# RF-PWR-001.net
KiCad netlist of a schematic drawn in EAGLE
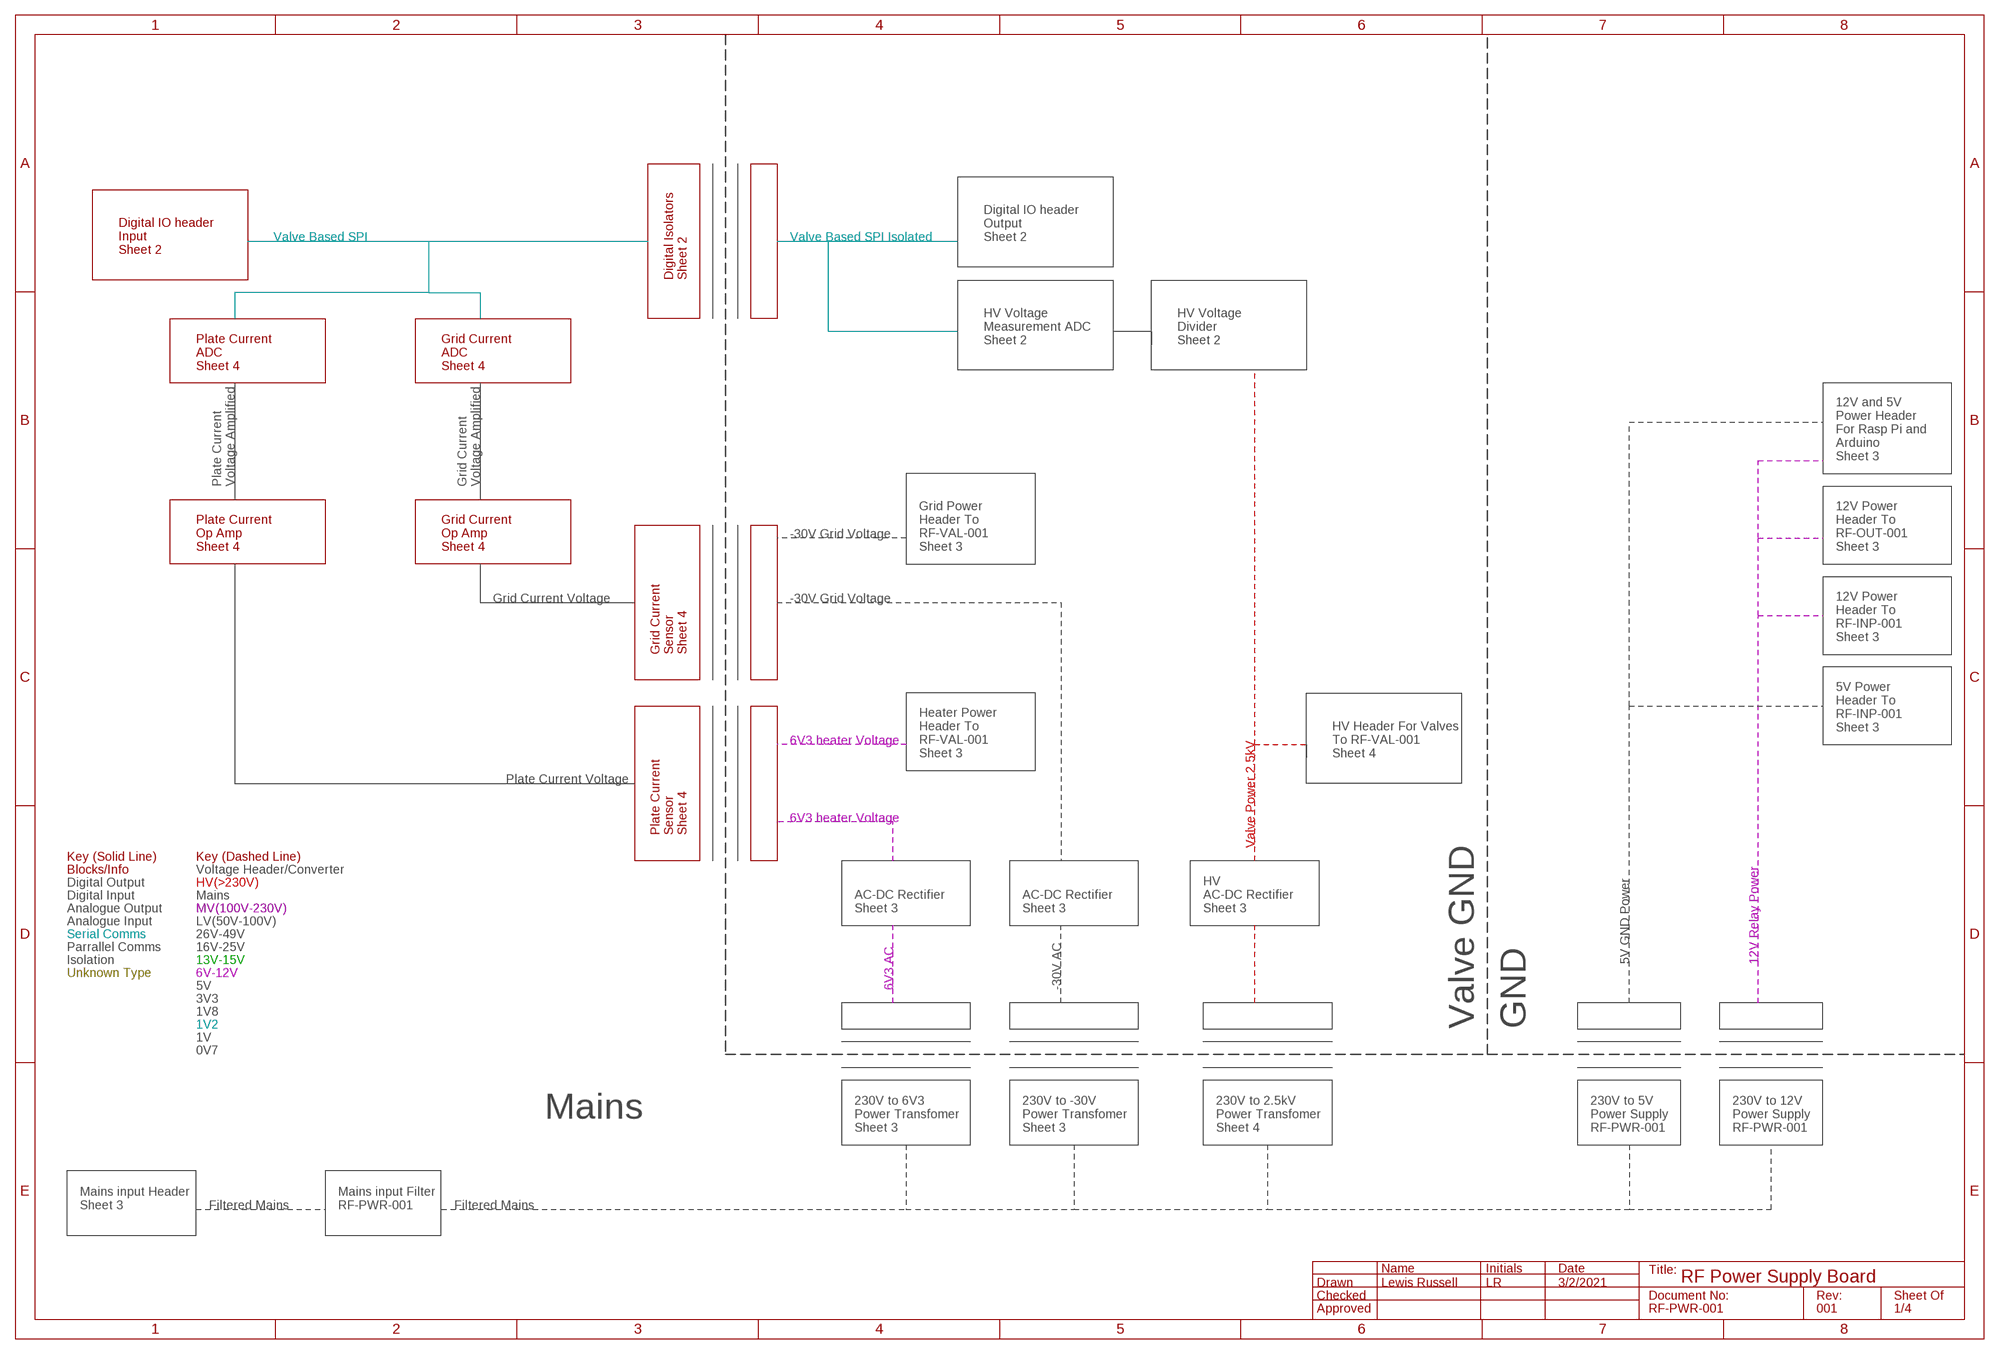
[diagram p0: schematic, sheet 1]
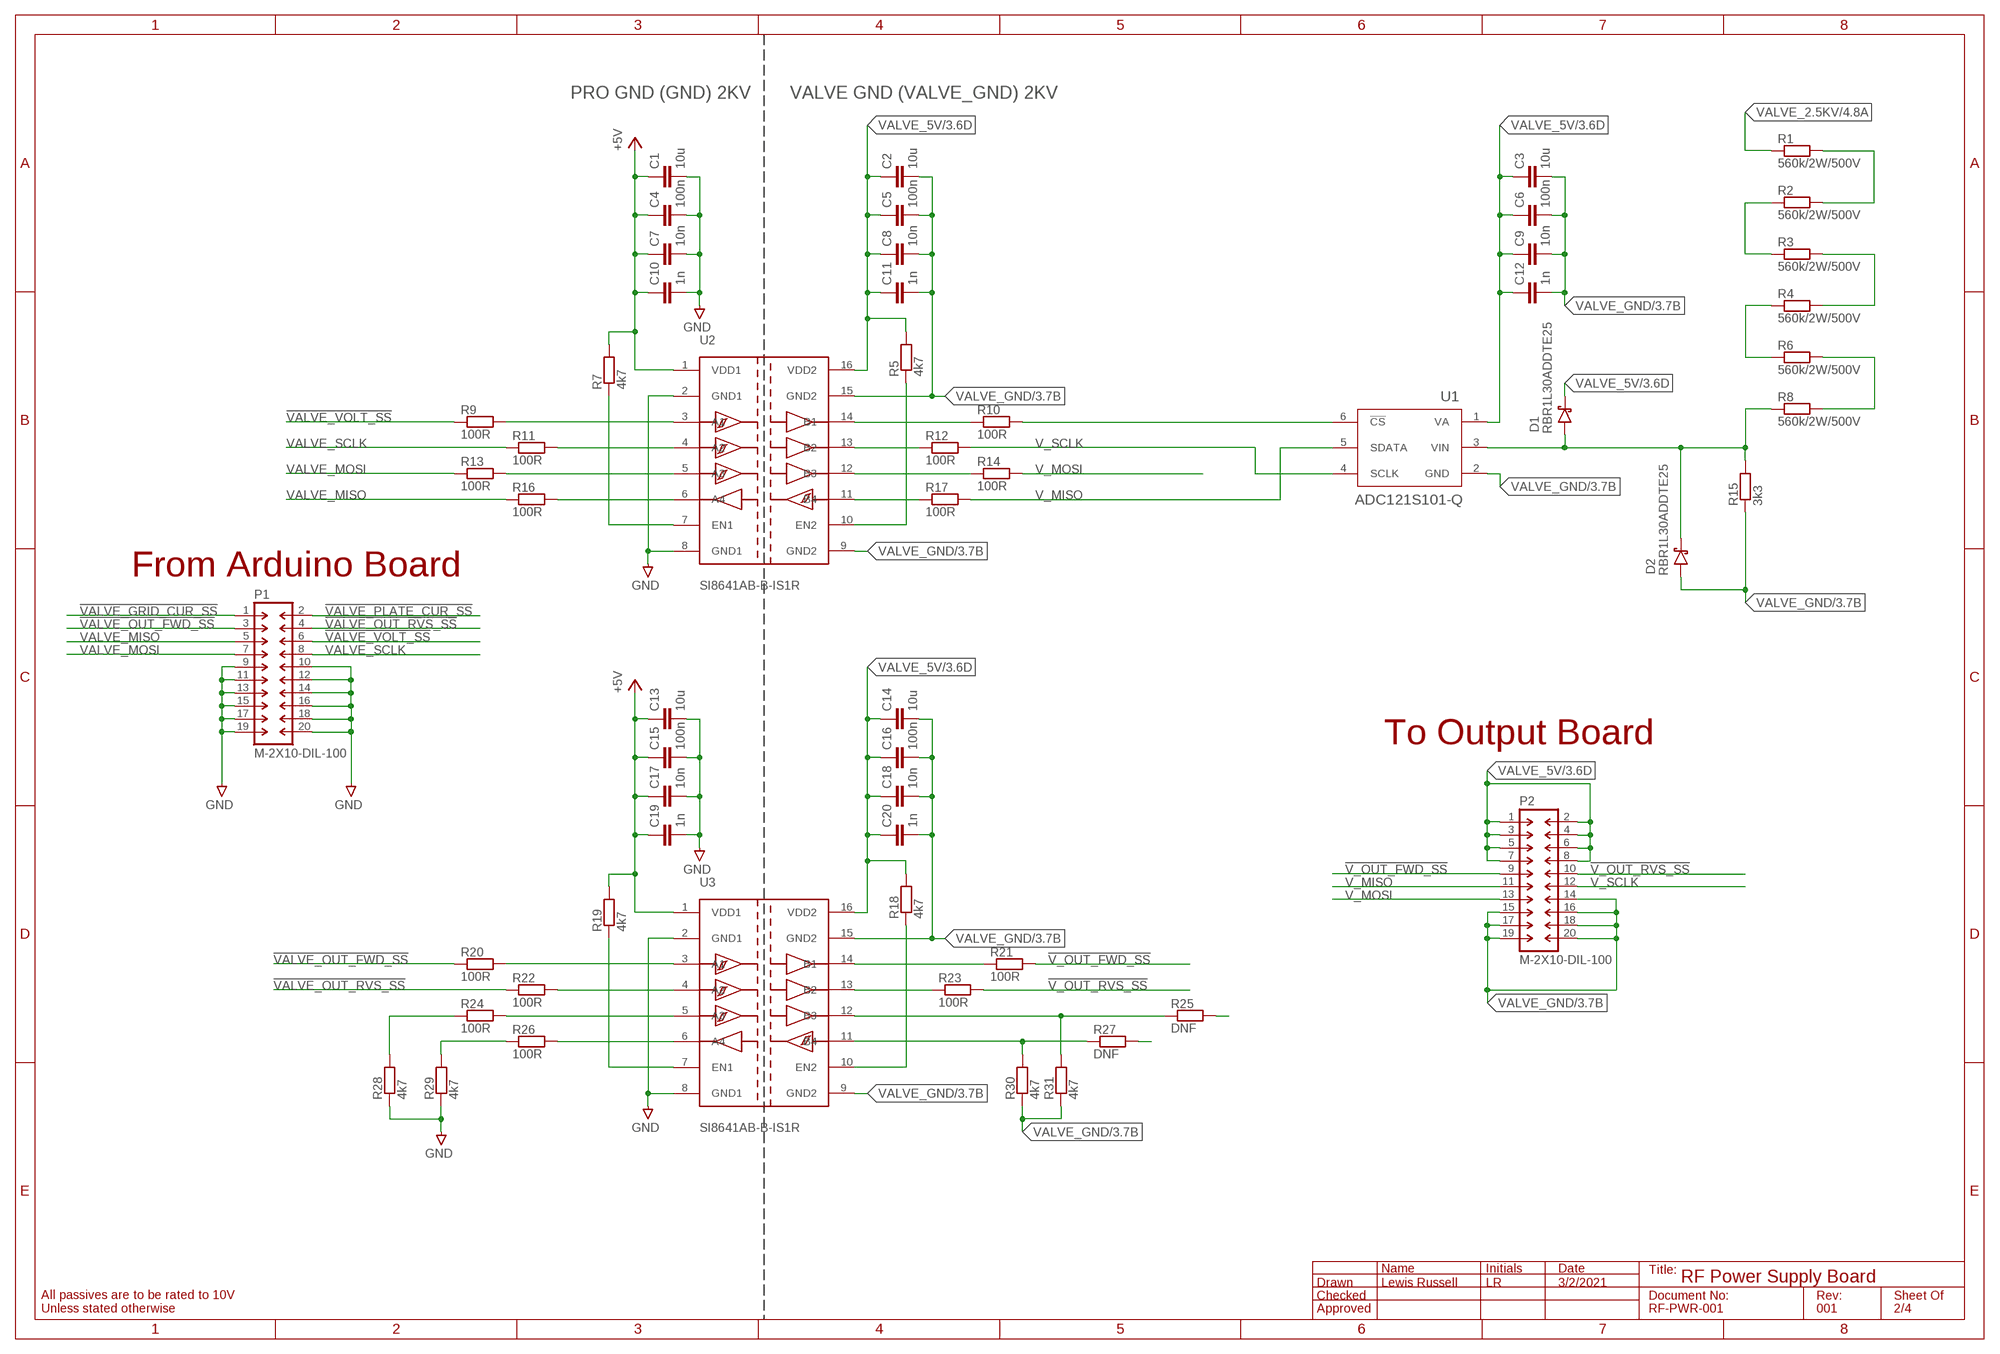
[diagram p1: schematic, sheet 2]
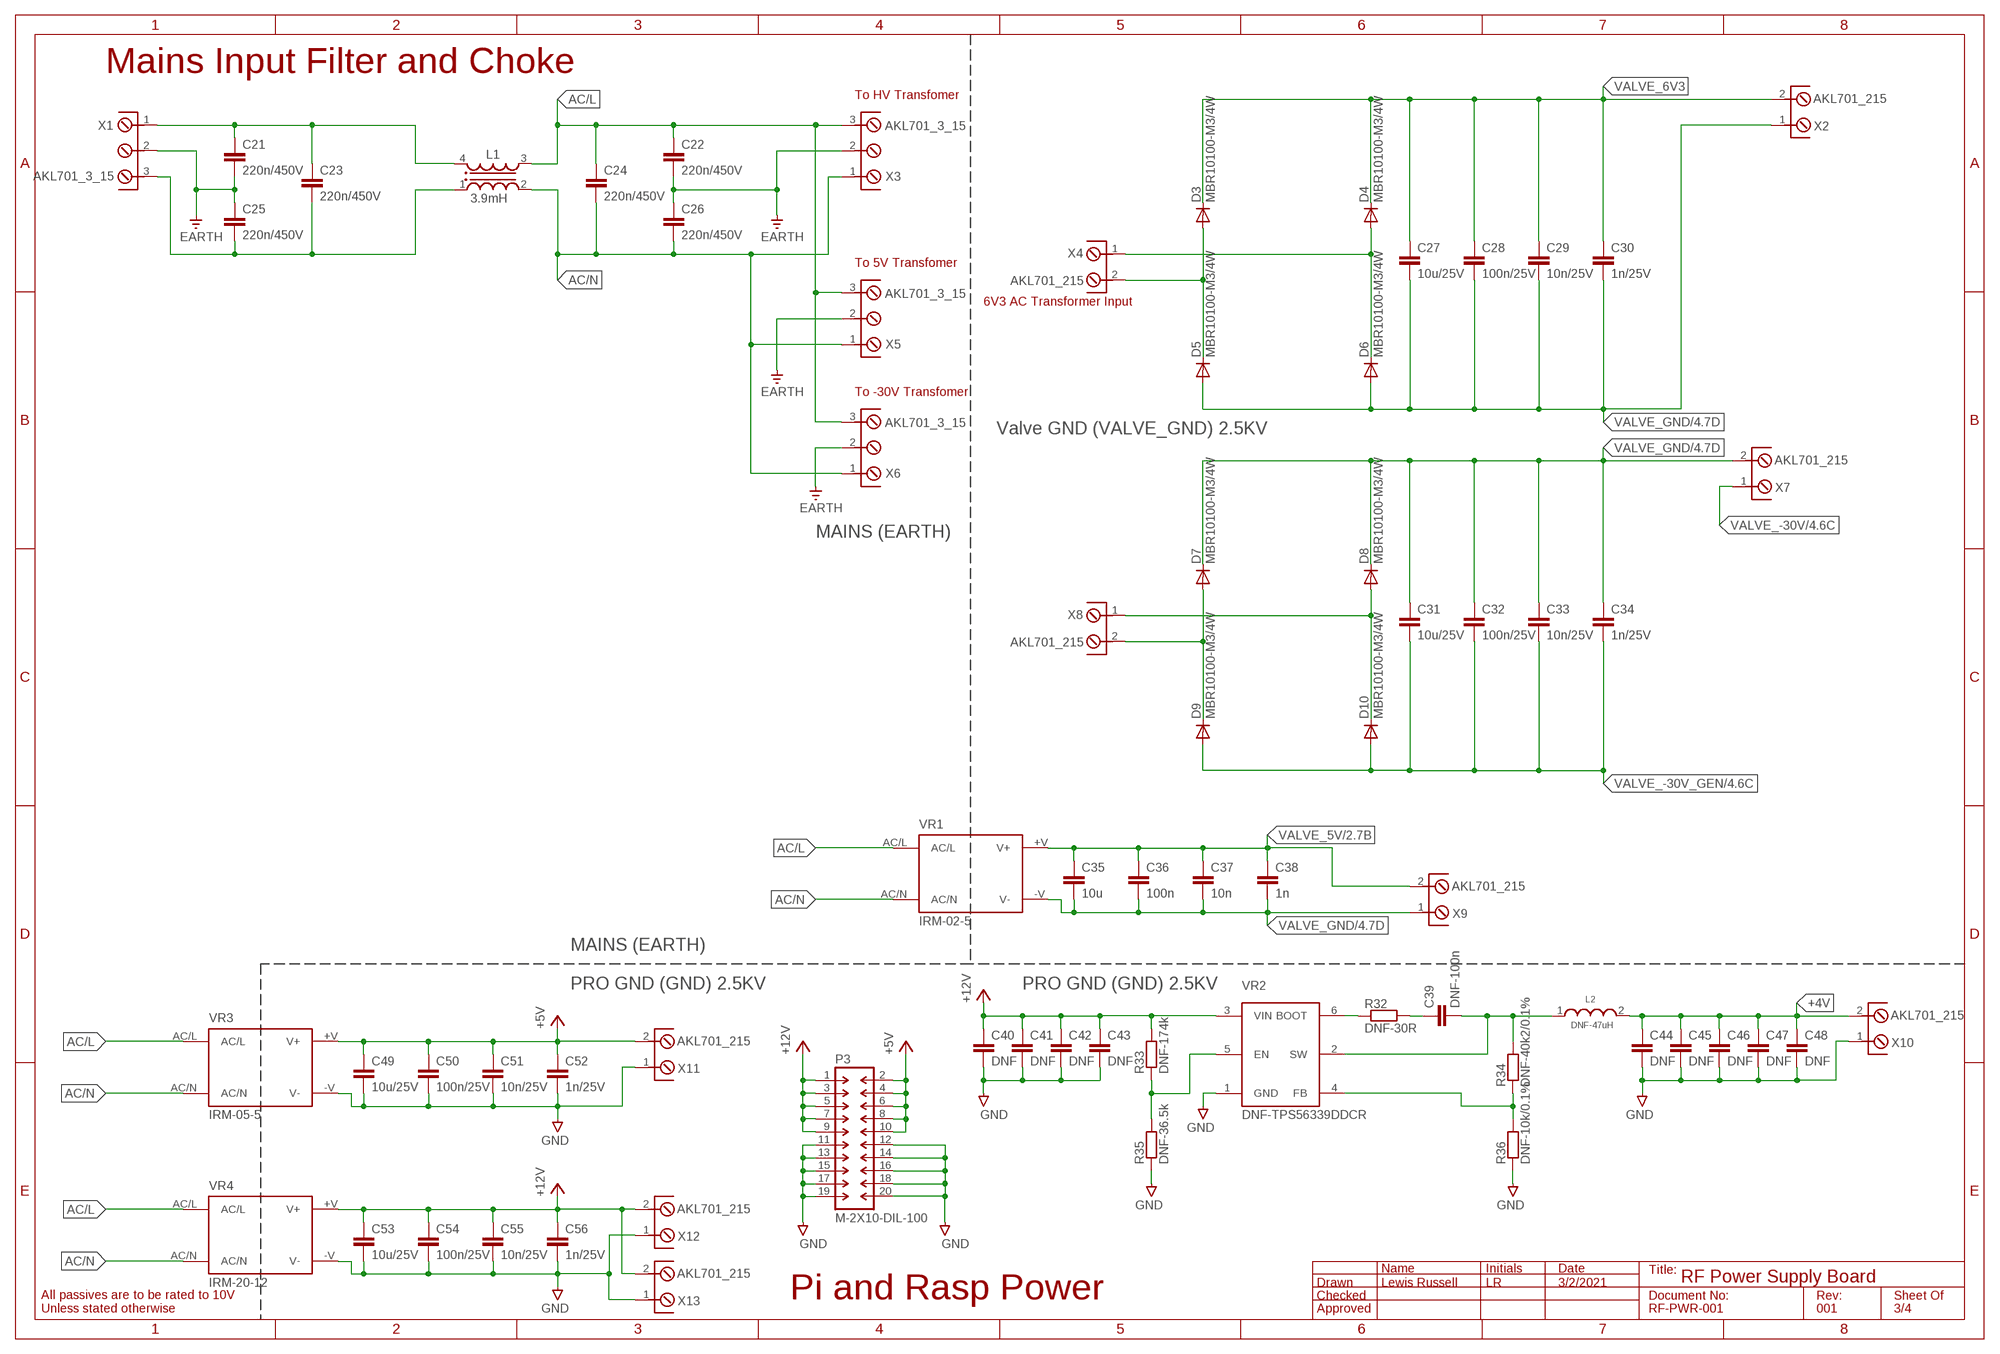
[diagram p2: schematic, sheet 3]
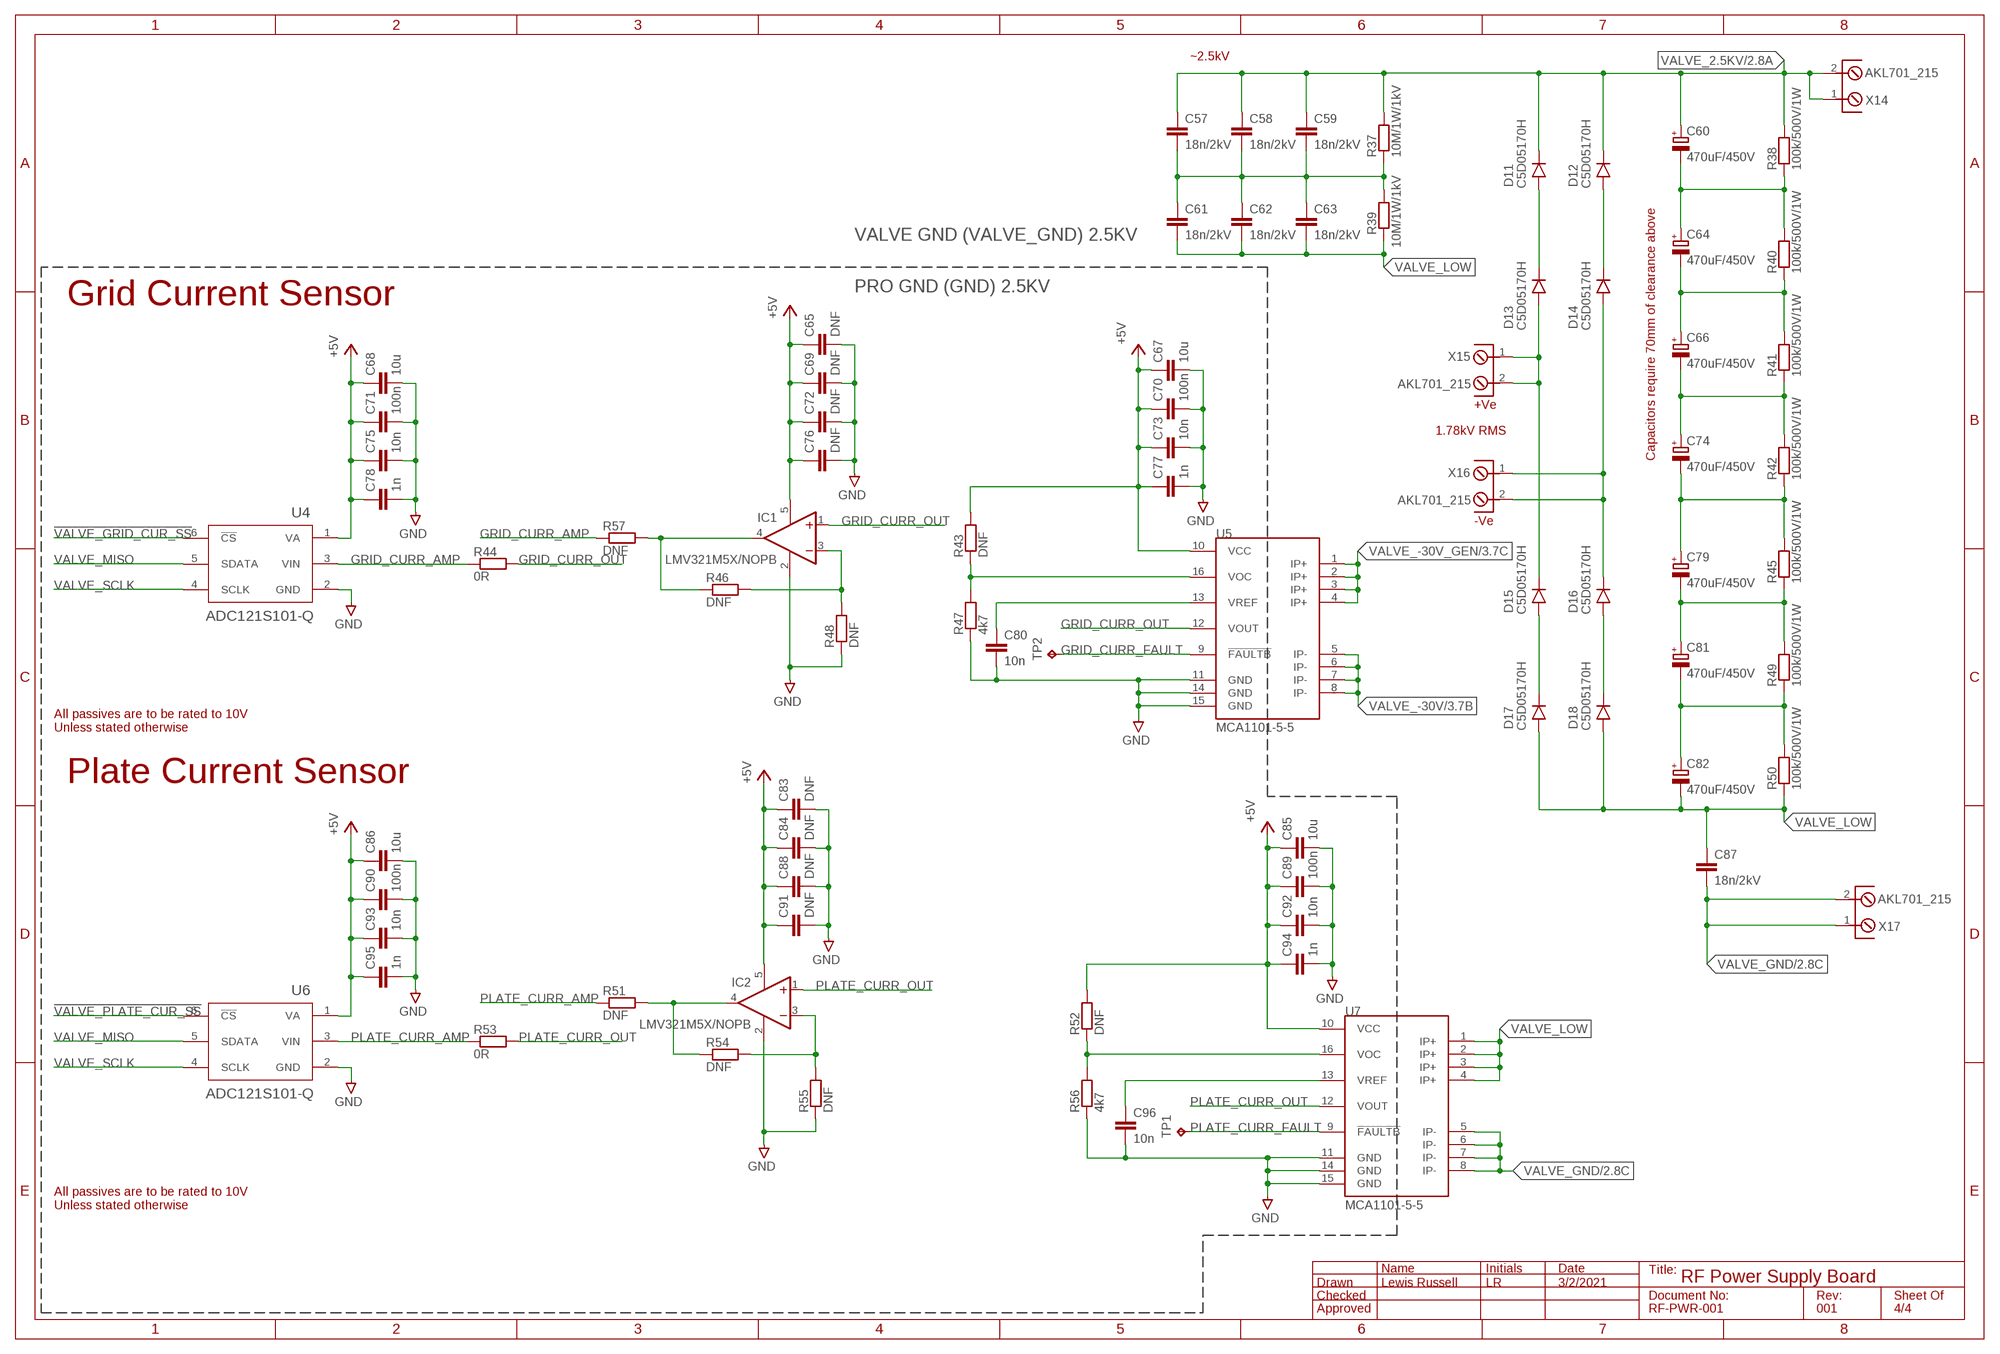
[diagram p3: schematic, sheet 4]

(export (version "E")
  (design (tool "Eeschema 10.0.6"))
  (components
    (comp (ref "C57")
      (value "18n/2kV")
      (footprint "eagle-import:C050-075X075")
      (libsource (lib "eagle-import") (part "C-EU050-075X075"))
    )
    (comp (ref "C58")
      (value "18n/2kV")
      (footprint "eagle-import:C050-075X075")
      (libsource (lib "eagle-import") (part "C-EU050-075X075"))
    )
    (comp (ref "C59")
      (value "18n/2kV")
      (footprint "eagle-import:C050-075X075")
      (libsource (lib "eagle-import") (part "C-EU050-075X075"))
    )
    (comp (ref "C60")
      (value "470uF/450V")
      (footprint "eagle-import:STYLE_D(35MM)")
      (libsource (lib "eagle-import") (part "ALC10D-35MM"))
    )
    (comp (ref "C61")
      (value "18n/2kV")
      (footprint "eagle-import:C050-075X075")
      (libsource (lib "eagle-import") (part "C-EU050-075X075"))
    )
    (comp (ref "C62")
      (value "18n/2kV")
      (footprint "eagle-import:C050-075X075")
      (libsource (lib "eagle-import") (part "C-EU050-075X075"))
    )
    (comp (ref "C63")
      (value "18n/2kV")
      (footprint "eagle-import:C050-075X075")
      (libsource (lib "eagle-import") (part "C-EU050-075X075"))
    )
    (comp (ref "C64")
      (value "470uF/450V")
      (footprint "eagle-import:STYLE_D(35MM)")
      (libsource (lib "eagle-import") (part "ALC10D-35MM"))
    )
    (comp (ref "C65")
      (value "DNF")
      (footprint "eagle-import:C0805")
      (libsource (lib "eagle-import") (part "C-EUC0805"))
    )
    (comp (ref "C66")
      (value "470uF/450V")
      (footprint "eagle-import:STYLE_D(35MM)")
      (libsource (lib "eagle-import") (part "ALC10D-35MM"))
    )
    (comp (ref "C67")
      (value "10u")
      (footprint "eagle-import:C0805")
      (libsource (lib "eagle-import") (part "C-EUC0805"))
    )
    (comp (ref "C68")
      (value "10u")
      (footprint "eagle-import:C0805")
      (libsource (lib "eagle-import") (part "C-EUC0805"))
    )
    (comp (ref "C69")
      (value "DNF")
      (footprint "eagle-import:C0603")
      (libsource (lib "eagle-import") (part "C-EUC0603"))
    )
    (comp (ref "C70")
      (value "100n")
      (footprint "eagle-import:C0603")
      (libsource (lib "eagle-import") (part "C-EUC0603"))
    )
    (comp (ref "C71")
      (value "100n")
      (footprint "eagle-import:C0603")
      (libsource (lib "eagle-import") (part "C-EUC0603"))
    )
    (comp (ref "C72")
      (value "DNF")
      (footprint "eagle-import:C0603")
      (libsource (lib "eagle-import") (part "C-EUC0603"))
    )
    (comp (ref "C73")
      (value "10n")
      (footprint "eagle-import:C0603")
      (libsource (lib "eagle-import") (part "C-EUC0603"))
    )
    (comp (ref "C74")
      (value "470uF/450V")
      (footprint "eagle-import:STYLE_D(35MM)")
      (libsource (lib "eagle-import") (part "ALC10D-35MM"))
    )
    (comp (ref "C75")
      (value "10n")
      (footprint "eagle-import:C0603")
      (libsource (lib "eagle-import") (part "C-EUC0603"))
    )
    (comp (ref "C76")
      (value "DNF")
      (footprint "eagle-import:C0603")
      (libsource (lib "eagle-import") (part "C-EUC0603"))
    )
    (comp (ref "C77")
      (value "1n")
      (footprint "eagle-import:C0603")
      (libsource (lib "eagle-import") (part "C-EUC0603"))
    )
    (comp (ref "C78")
      (value "1n")
      (footprint "eagle-import:C0603")
      (libsource (lib "eagle-import") (part "C-EUC0603"))
    )
    (comp (ref "C79")
      (value "470uF/450V")
      (footprint "eagle-import:STYLE_D(35MM)")
      (libsource (lib "eagle-import") (part "ALC10D-35MM"))
    )
    (comp (ref "C80")
      (value "10n")
      (footprint "eagle-import:C0603")
      (libsource (lib "eagle-import") (part "C-EUC0603"))
    )
    (comp (ref "C81")
      (value "470uF/450V")
      (footprint "eagle-import:STYLE_D(35MM)")
      (libsource (lib "eagle-import") (part "ALC10D-35MM"))
    )
    (comp (ref "C82")
      (value "470uF/450V")
      (footprint "eagle-import:STYLE_D(35MM)")
      (libsource (lib "eagle-import") (part "ALC10D-35MM"))
    )
    (comp (ref "C83")
      (value "DNF")
      (footprint "eagle-import:C0805")
      (libsource (lib "eagle-import") (part "C-EUC0805"))
    )
    (comp (ref "C84")
      (value "DNF")
      (footprint "eagle-import:C0603")
      (libsource (lib "eagle-import") (part "C-EUC0603"))
    )
    (comp (ref "C85")
      (value "10u")
      (footprint "eagle-import:C0805")
      (libsource (lib "eagle-import") (part "C-EUC0805"))
    )
    (comp (ref "C86")
      (value "10u")
      (footprint "eagle-import:C0805")
      (libsource (lib "eagle-import") (part "C-EUC0805"))
    )
    (comp (ref "C87")
      (value "18n/2kV")
      (footprint "eagle-import:C050-075X075")
      (libsource (lib "eagle-import") (part "C-EU050-075X075"))
    )
    (comp (ref "C88")
      (value "DNF")
      (footprint "eagle-import:C0603")
      (libsource (lib "eagle-import") (part "C-EUC0603"))
    )
    (comp (ref "C89")
      (value "100n")
      (footprint "eagle-import:C0603")
      (libsource (lib "eagle-import") (part "C-EUC0603"))
    )
    (comp (ref "C90")
      (value "100n")
      (footprint "eagle-import:C0603")
      (libsource (lib "eagle-import") (part "C-EUC0603"))
    )
    (comp (ref "C91")
      (value "DNF")
      (footprint "eagle-import:C0603")
      (libsource (lib "eagle-import") (part "C-EUC0603"))
    )
    (comp (ref "C92")
      (value "10n")
      (footprint "eagle-import:C0603")
      (libsource (lib "eagle-import") (part "C-EUC0603"))
    )
    (comp (ref "C93")
      (value "10n")
      (footprint "eagle-import:C0603")
      (libsource (lib "eagle-import") (part "C-EUC0603"))
    )
    (comp (ref "C94")
      (value "1n")
      (footprint "eagle-import:C0603")
      (libsource (lib "eagle-import") (part "C-EUC0603"))
    )
    (comp (ref "C95")
      (value "1n")
      (footprint "eagle-import:C0603")
      (libsource (lib "eagle-import") (part "C-EUC0603"))
    )
    (comp (ref "C96")
      (value "10n")
      (footprint "eagle-import:C0603")
      (libsource (lib "eagle-import") (part "C-EUC0603"))
    )
    (comp (ref "D11")
      (value "C5D05170H")
      (footprint "eagle-import:TO-247-2")
      (libsource (lib "eagle-import") (part "DIODEC1A3-2"))
    )
    (comp (ref "D12")
      (value "C5D05170H")
      (footprint "eagle-import:TO-247-2")
      (libsource (lib "eagle-import") (part "DIODEC1A3-2"))
    )
    (comp (ref "D13")
      (value "C5D05170H")
      (footprint "eagle-import:TO-247-2")
      (libsource (lib "eagle-import") (part "DIODEC1A3-2"))
    )
    (comp (ref "D14")
      (value "C5D05170H")
      (footprint "eagle-import:TO-247-2")
      (libsource (lib "eagle-import") (part "DIODEC1A3-2"))
    )
    (comp (ref "D15")
      (value "C5D05170H")
      (footprint "eagle-import:TO-247-2")
      (libsource (lib "eagle-import") (part "DIODEC1A3-2"))
    )
    (comp (ref "D16")
      (value "C5D05170H")
      (footprint "eagle-import:TO-247-2")
      (libsource (lib "eagle-import") (part "DIODEC1A3-2"))
    )
    (comp (ref "D17")
      (value "C5D05170H")
      (footprint "eagle-import:TO-247-2")
      (libsource (lib "eagle-import") (part "DIODEC1A3-2"))
    )
    (comp (ref "D18")
      (value "C5D05170H")
      (footprint "eagle-import:TO-247-2")
      (libsource (lib "eagle-import") (part "DIODEC1A3-2"))
    )
    (comp (ref "IC1")
      (value "LMV321M5X/NOPB")
      (footprint "eagle-import:SOT23-5")
      (libsource (lib "eagle-import") (part "LMV321?M5"))
    )
    (comp (ref "IC2")
      (value "LMV321M5X/NOPB")
      (footprint "eagle-import:SOT23-5")
      (libsource (lib "eagle-import") (part "LMV321?M5"))
    )
    (comp (ref "R37")
      (value "10M/1W/1kV")
      (footprint "eagle-import:R2512")
      (libsource (lib "eagle-import") (part "R-EUR2512"))
    )
    (comp (ref "R38")
      (value "100k/500V/1W")
      (footprint "eagle-import:R2512")
      (libsource (lib "eagle-import") (part "R-EUR2512"))
    )
    (comp (ref "R39")
      (value "10M/1W/1kV")
      (footprint "eagle-import:R2512")
      (libsource (lib "eagle-import") (part "R-EUR2512"))
    )
    (comp (ref "R40")
      (value "100k/500V/1W")
      (footprint "eagle-import:R2512")
      (libsource (lib "eagle-import") (part "R-EUR2512"))
    )
    (comp (ref "R41")
      (value "100k/500V/1W")
      (footprint "eagle-import:R2512")
      (libsource (lib "eagle-import") (part "R-EUR2512"))
    )
    (comp (ref "R42")
      (value "100k/500V/1W")
      (footprint "eagle-import:R2512")
      (libsource (lib "eagle-import") (part "R-EUR2512"))
    )
    (comp (ref "R43")
      (value "DNF")
      (footprint "eagle-import:R0603")
      (libsource (lib "eagle-import") (part "R-EUR0603"))
    )
    (comp (ref "R44")
      (value "0R")
      (footprint "eagle-import:R0603")
      (libsource (lib "eagle-import") (part "R-EUR0603"))
    )
    (comp (ref "R45")
      (value "100k/500V/1W")
      (footprint "eagle-import:R2512")
      (libsource (lib "eagle-import") (part "R-EUR2512"))
    )
    (comp (ref "R46")
      (value "DNF")
      (footprint "eagle-import:R0603")
      (libsource (lib "eagle-import") (part "R-EUR0603"))
    )
    (comp (ref "R47")
      (value "4k7")
      (footprint "eagle-import:R0603")
      (libsource (lib "eagle-import") (part "R-EUR0603"))
    )
    (comp (ref "R48")
      (value "DNF")
      (footprint "eagle-import:R0603")
      (libsource (lib "eagle-import") (part "R-EUR0603"))
    )
    (comp (ref "R49")
      (value "100k/500V/1W")
      (footprint "eagle-import:R2512")
      (libsource (lib "eagle-import") (part "R-EUR2512"))
    )
    (comp (ref "R50")
      (value "100k/500V/1W")
      (footprint "eagle-import:R2512")
      (libsource (lib "eagle-import") (part "R-EUR2512"))
    )
    (comp (ref "R51")
      (value "DNF")
      (footprint "eagle-import:R0603")
      (libsource (lib "eagle-import") (part "R-EUR0603"))
    )
    (comp (ref "R52")
      (value "DNF")
      (footprint "eagle-import:R0603")
      (libsource (lib "eagle-import") (part "R-EUR0603"))
    )
    (comp (ref "R53")
      (value "0R")
      (footprint "eagle-import:R0603")
      (libsource (lib "eagle-import") (part "R-EUR0603"))
    )
    (comp (ref "R54")
      (value "DNF")
      (footprint "eagle-import:R0603")
      (libsource (lib "eagle-import") (part "R-EUR0603"))
    )
    (comp (ref "R55")
      (value "DNF")
      (footprint "eagle-import:R0603")
      (libsource (lib "eagle-import") (part "R-EUR0603"))
    )
    (comp (ref "R56")
      (value "4k7")
      (footprint "eagle-import:R0603")
      (libsource (lib "eagle-import") (part "R-EUR0603"))
    )
    (comp (ref "R57")
      (value "DNF")
      (footprint "eagle-import:R0603")
      (libsource (lib "eagle-import") (part "R-EUR0603"))
    )
    (comp (ref "TP1")
      (value "TPTP16R")
      (footprint "eagle-import:TP16R")
      (libsource (lib "eagle-import") (part "TPTP16R"))
    )
    (comp (ref "TP2")
      (value "TPTP16R")
      (footprint "eagle-import:TP16R")
      (libsource (lib "eagle-import") (part "TPTP16R"))
    )
    (comp (ref "U4")
      (value "ADC121S101-Q")
      (footprint "eagle-import:SOT23-6")
      (libsource (lib "eagle-import") (part "ADC121S101-Q"))
    )
    (comp (ref "U5")
      (value "MCA1101-5-5")
      (footprint "eagle-import:SOIC_16")
      (libsource (lib "eagle-import") (part "MCA1101-5-5"))
    )
    (comp (ref "U6")
      (value "ADC121S101-Q")
      (footprint "eagle-import:SOT23-6")
      (libsource (lib "eagle-import") (part "ADC121S101-Q"))
    )
    (comp (ref "U7")
      (value "MCA1101-5-5")
      (footprint "eagle-import:SOIC_16")
      (libsource (lib "eagle-import") (part "MCA1101-5-5"))
    )
    (comp (ref "X14")
      (value "AKL701_215")
      (footprint "eagle-import:AKL701_2_15")
      (libsource (lib "eagle-import") (part "AKL701_215"))
    )
    (comp (ref "X15")
      (value "AKL701_215")
      (footprint "eagle-import:AKL701_2_15")
      (libsource (lib "eagle-import") (part "AKL701_215"))
    )
    (comp (ref "X16")
      (value "AKL701_215")
      (footprint "eagle-import:AKL701_2_15")
      (libsource (lib "eagle-import") (part "AKL701_215"))
    )
    (comp (ref "X17")
      (value "AKL701_215")
      (footprint "eagle-import:AKL701_2_15")
      (libsource (lib "eagle-import") (part "AKL701_215"))
    )
    (comp (ref "C21")
      (value "220n/450V")
      (footprint "eagle-import:C1210")
      (libsource (lib "eagle-import") (part "C-EUC1210"))
    )
    (comp (ref "C22")
      (value "220n/450V")
      (footprint "eagle-import:C1210")
      (libsource (lib "eagle-import") (part "C-EUC1210"))
    )
    (comp (ref "C23")
      (value "220n/450V")
      (footprint "eagle-import:C1210")
      (libsource (lib "eagle-import") (part "C-EUC1210"))
    )
    (comp (ref "C24")
      (value "220n/450V")
      (footprint "eagle-import:C1210")
      (libsource (lib "eagle-import") (part "C-EUC1210"))
    )
    (comp (ref "C25")
      (value "220n/450V")
      (footprint "eagle-import:C1210")
      (libsource (lib "eagle-import") (part "C-EUC1210"))
    )
    (comp (ref "C26")
      (value "220n/450V")
      (footprint "eagle-import:C1210")
      (libsource (lib "eagle-import") (part "C-EUC1210"))
    )
    (comp (ref "C27")
      (value "10u/25V")
      (footprint "eagle-import:C0805")
      (libsource (lib "eagle-import") (part "C-EUC0805"))
    )
    (comp (ref "C28")
      (value "100n/25V")
      (footprint "eagle-import:C0603")
      (libsource (lib "eagle-import") (part "C-EUC0603"))
    )
    (comp (ref "C29")
      (value "10n/25V")
      (footprint "eagle-import:C0603")
      (libsource (lib "eagle-import") (part "C-EUC0603"))
    )
    (comp (ref "C30")
      (value "1n/25V")
      (footprint "eagle-import:C0603")
      (libsource (lib "eagle-import") (part "C-EUC0603"))
    )
    (comp (ref "C31")
      (value "10u/25V")
      (footprint "eagle-import:C0805")
      (libsource (lib "eagle-import") (part "C-EUC0805"))
    )
    (comp (ref "C32")
      (value "100n/25V")
      (footprint "eagle-import:C0603")
      (libsource (lib "eagle-import") (part "C-EUC0603"))
    )
    (comp (ref "C33")
      (value "10n/25V")
      (footprint "eagle-import:C0603")
      (libsource (lib "eagle-import") (part "C-EUC0603"))
    )
    (comp (ref "C34")
      (value "1n/25V")
      (footprint "eagle-import:C0603")
      (libsource (lib "eagle-import") (part "C-EUC0603"))
    )
    (comp (ref "C35")
      (value "10u")
      (footprint "eagle-import:C0805")
      (libsource (lib "eagle-import") (part "C-EUC0805"))
    )
    (comp (ref "C36")
      (value "100n")
      (footprint "eagle-import:C0603")
      (libsource (lib "eagle-import") (part "C-EUC0603"))
    )
    (comp (ref "C37")
      (value "10n")
      (footprint "eagle-import:C0603")
      (libsource (lib "eagle-import") (part "C-EUC0603"))
    )
    (comp (ref "C38")
      (value "1n")
      (footprint "eagle-import:C0603")
      (libsource (lib "eagle-import") (part "C-EUC0603"))
    )
    (comp (ref "C39")
      (value "DNF-100n")
      (footprint "eagle-import:C0603")
      (libsource (lib "eagle-import") (part "C-EUC0603"))
    )
    (comp (ref "C40")
      (value "DNF")
      (footprint "eagle-import:C0805")
      (libsource (lib "eagle-import") (part "C-EUC0805"))
    )
    (comp (ref "C41")
      (value "DNF")
      (footprint "eagle-import:C0603")
      (libsource (lib "eagle-import") (part "C-EUC0603"))
    )
    (comp (ref "C42")
      (value "DNF")
      (footprint "eagle-import:C0603")
      (libsource (lib "eagle-import") (part "C-EUC0603"))
    )
    (comp (ref "C43")
      (value "DNF")
      (footprint "eagle-import:C0603")
      (libsource (lib "eagle-import") (part "C-EUC0603"))
    )
    (comp (ref "C44")
      (value "DNF")
      (footprint "eagle-import:C1206")
      (libsource (lib "eagle-import") (part "C-EUC1206"))
    )
    (comp (ref "C45")
      (value "DNF")
      (footprint "eagle-import:C0805")
      (libsource (lib "eagle-import") (part "C-EUC0805"))
    )
    (comp (ref "C46")
      (value "DNF")
      (footprint "eagle-import:C0603")
      (libsource (lib "eagle-import") (part "C-EUC0603"))
    )
    (comp (ref "C47")
      (value "DNF")
      (footprint "eagle-import:C0603")
      (libsource (lib "eagle-import") (part "C-EUC0603"))
    )
    (comp (ref "C48")
      (value "DNF")
      (footprint "eagle-import:C0603")
      (libsource (lib "eagle-import") (part "C-EUC0603"))
    )
    (comp (ref "C49")
      (value "10u/25V")
      (footprint "eagle-import:C0805")
      (libsource (lib "eagle-import") (part "C-EUC0805"))
    )
    (comp (ref "C50")
      (value "100n/25V")
      (footprint "eagle-import:C0603")
      (libsource (lib "eagle-import") (part "C-EUC0603"))
    )
    (comp (ref "C51")
      (value "10n/25V")
      (footprint "eagle-import:C0603")
      (libsource (lib "eagle-import") (part "C-EUC0603"))
    )
    (comp (ref "C52")
      (value "1n/25V")
      (footprint "eagle-import:C0603")
      (libsource (lib "eagle-import") (part "C-EUC0603"))
    )
    (comp (ref "C53")
      (value "10u/25V")
      (footprint "eagle-import:C0805")
      (libsource (lib "eagle-import") (part "C-EUC0805"))
    )
    (comp (ref "C54")
      (value "100n/25V")
      (footprint "eagle-import:C0603")
      (libsource (lib "eagle-import") (part "C-EUC0603"))
    )
    (comp (ref "C55")
      (value "10n/25V")
      (footprint "eagle-import:C0603")
      (libsource (lib "eagle-import") (part "C-EUC0603"))
    )
    (comp (ref "C56")
      (value "1n/25V")
      (footprint "eagle-import:C0603")
      (libsource (lib "eagle-import") (part "C-EUC0603"))
    )
    (comp (ref "D3")
      (value "MBR10100-M3/4W")
      (footprint "eagle-import:TO220ACS")
      (libsource (lib "eagle-import") (part "DIODE-TO220V"))
    )
    (comp (ref "D4")
      (value "MBR10100-M3/4W")
      (footprint "eagle-import:TO220ACS")
      (libsource (lib "eagle-import") (part "DIODE-TO220V"))
    )
    (comp (ref "D5")
      (value "MBR10100-M3/4W")
      (footprint "eagle-import:TO220ACS")
      (libsource (lib "eagle-import") (part "DIODE-TO220V"))
    )
    (comp (ref "D6")
      (value "MBR10100-M3/4W")
      (footprint "eagle-import:TO220ACS")
      (libsource (lib "eagle-import") (part "DIODE-TO220V"))
    )
    (comp (ref "D7")
      (value "MBR10100-M3/4W")
      (footprint "eagle-import:TO220ACS")
      (libsource (lib "eagle-import") (part "DIODE-TO220V"))
    )
    (comp (ref "D8")
      (value "MBR10100-M3/4W")
      (footprint "eagle-import:TO220ACS")
      (libsource (lib "eagle-import") (part "DIODE-TO220V"))
    )
    (comp (ref "D9")
      (value "MBR10100-M3/4W")
      (footprint "eagle-import:TO220ACS")
      (libsource (lib "eagle-import") (part "DIODE-TO220V"))
    )
    (comp (ref "D10")
      (value "MBR10100-M3/4W")
      (footprint "eagle-import:TO220ACS")
      (libsource (lib "eagle-import") (part "DIODE-TO220V"))
    )
    (comp (ref "L1")
      (value "3.9mH")
      (footprint "eagle-import:WE-FCL_ET35")
      (libsource (lib "eagle-import") (part "WE-FCL_ET35_744866392"))
    )
    (comp (ref "L2")
      (value "DNF-47uH")
      (footprint "eagle-import:WE-HCF_2920_ROUND")
      (libsource (lib "eagle-import") (part "WE-HCF_2920_ROUND_74437529203470"))
    )
    (comp (ref "P3")
      (value "M-2X10-DIL-100")
      (footprint "eagle-import:DIL-100-2X10")
      (libsource (lib "eagle-import") (part "M-2X10-DIL-100"))
    )
    (comp (ref "R32")
      (value "DNF-30R")
      (footprint "eagle-import:R0603")
      (libsource (lib "eagle-import") (part "R-EUR0603"))
    )
    (comp (ref "R33")
      (value "DNF-174k")
      (footprint "eagle-import:R0603")
      (libsource (lib "eagle-import") (part "R-EUR0603"))
    )
    (comp (ref "R34")
      (value "DNF-40k2/0.1%")
      (footprint "eagle-import:R0603")
      (libsource (lib "eagle-import") (part "R-EUR0603"))
    )
    (comp (ref "R35")
      (value "DNF-36.5k")
      (footprint "eagle-import:R0603")
      (libsource (lib "eagle-import") (part "R-EUR0603"))
    )
    (comp (ref "R36")
      (value "DNF-10k/0.1%")
      (footprint "eagle-import:R0603")
      (libsource (lib "eagle-import") (part "R-EUR0603"))
    )
    (comp (ref "VR1")
      (value "IRM-02-5")
      (footprint "eagle-import:IRM_1-2_TH")
      (libsource (lib "eagle-import") (part "IRM-02-5"))
    )
    (comp (ref "VR2")
      (value "DNF-TPS56339DDCR")
      (footprint "eagle-import:SOT23-6")
      (libsource (lib "eagle-import") (part "TPS56339DDCR"))
    )
    (comp (ref "VR3")
      (value "IRM-05-5")
      (footprint "eagle-import:IRM_5-10_TH")
      (libsource (lib "eagle-import") (part "IRM-05-5"))
    )
    (comp (ref "VR4")
      (value "IRM-20-12")
      (footprint "eagle-import:IRM_15-20_TH")
      (libsource (lib "eagle-import") (part "IRM-20-12"))
    )
    (comp (ref "X1")
      (value "AKL701_3_15")
      (footprint "eagle-import:AKL701_3_15")
      (libsource (lib "eagle-import") (part "AKL701_3_15"))
    )
    (comp (ref "X2")
      (value "AKL701_215")
      (footprint "eagle-import:AKL701_2_15")
      (libsource (lib "eagle-import") (part "AKL701_215"))
    )
    (comp (ref "X3")
      (value "AKL701_3_15")
      (footprint "eagle-import:AKL701_3_15")
      (libsource (lib "eagle-import") (part "AKL701_3_15"))
    )
    (comp (ref "X4")
      (value "AKL701_215")
      (footprint "eagle-import:AKL701_2_15")
      (libsource (lib "eagle-import") (part "AKL701_215"))
    )
    (comp (ref "X5")
      (value "AKL701_3_15")
      (footprint "eagle-import:AKL701_3_15")
      (libsource (lib "eagle-import") (part "AKL701_3_15"))
    )
    (comp (ref "X6")
      (value "AKL701_3_15")
      (footprint "eagle-import:AKL701_3_15")
      (libsource (lib "eagle-import") (part "AKL701_3_15"))
    )
    (comp (ref "X7")
      (value "AKL701_215")
      (footprint "eagle-import:AKL701_2_15")
      (libsource (lib "eagle-import") (part "AKL701_215"))
    )
    (comp (ref "X8")
      (value "AKL701_215")
      (footprint "eagle-import:AKL701_2_15")
      (libsource (lib "eagle-import") (part "AKL701_215"))
    )
    (comp (ref "X9")
      (value "AKL701_215")
      (footprint "eagle-import:AKL701_2_15")
      (libsource (lib "eagle-import") (part "AKL701_215"))
    )
    (comp (ref "X10")
      (value "AKL701_215")
      (footprint "eagle-import:AKL701_2_15")
      (libsource (lib "eagle-import") (part "AKL701_215"))
    )
    (comp (ref "X11")
      (value "AKL701_215")
      (footprint "eagle-import:AKL701_2_15")
      (libsource (lib "eagle-import") (part "AKL701_215"))
    )
    (comp (ref "X12")
      (value "AKL701_215")
      (footprint "eagle-import:AKL701_2_15")
      (libsource (lib "eagle-import") (part "AKL701_215"))
    )
    (comp (ref "X13")
      (value "AKL701_215")
      (footprint "eagle-import:AKL701_2_15")
      (libsource (lib "eagle-import") (part "AKL701_215"))
    )
    (comp (ref "C1")
      (value "10u")
      (footprint "eagle-import:C0805")
      (libsource (lib "eagle-import") (part "C-EUC0805"))
    )
    (comp (ref "C2")
      (value "10u")
      (footprint "eagle-import:C0805")
      (libsource (lib "eagle-import") (part "C-EUC0805"))
    )
    (comp (ref "C3")
      (value "10u")
      (footprint "eagle-import:C0805")
      (libsource (lib "eagle-import") (part "C-EUC0805"))
    )
    (comp (ref "C4")
      (value "100n")
      (footprint "eagle-import:C0603")
      (libsource (lib "eagle-import") (part "C-EUC0603"))
    )
    (comp (ref "C5")
      (value "100n")
      (footprint "eagle-import:C0603")
      (libsource (lib "eagle-import") (part "C-EUC0603"))
    )
    (comp (ref "C6")
      (value "100n")
      (footprint "eagle-import:C0603")
      (libsource (lib "eagle-import") (part "C-EUC0603"))
    )
    (comp (ref "C7")
      (value "10n")
      (footprint "eagle-import:C0603")
      (libsource (lib "eagle-import") (part "C-EUC0603"))
    )
    (comp (ref "C8")
      (value "10n")
      (footprint "eagle-import:C0603")
      (libsource (lib "eagle-import") (part "C-EUC0603"))
    )
    (comp (ref "C9")
      (value "10n")
      (footprint "eagle-import:C0603")
      (libsource (lib "eagle-import") (part "C-EUC0603"))
    )
    (comp (ref "C10")
      (value "1n")
      (footprint "eagle-import:C0603")
      (libsource (lib "eagle-import") (part "C-EUC0603"))
    )
    (comp (ref "C11")
      (value "1n")
      (footprint "eagle-import:C0603")
      (libsource (lib "eagle-import") (part "C-EUC0603"))
    )
    (comp (ref "C12")
      (value "1n")
      (footprint "eagle-import:C0603")
      (libsource (lib "eagle-import") (part "C-EUC0603"))
    )
    (comp (ref "C13")
      (value "10u")
      (footprint "eagle-import:C0805")
      (libsource (lib "eagle-import") (part "C-EUC0805"))
    )
    (comp (ref "C14")
      (value "10u")
      (footprint "eagle-import:C0805")
      (libsource (lib "eagle-import") (part "C-EUC0805"))
    )
    (comp (ref "C15")
      (value "100n")
      (footprint "eagle-import:C0603")
      (libsource (lib "eagle-import") (part "C-EUC0603"))
    )
    (comp (ref "C16")
      (value "100n")
      (footprint "eagle-import:C0603")
      (libsource (lib "eagle-import") (part "C-EUC0603"))
    )
    (comp (ref "C17")
      (value "10n")
      (footprint "eagle-import:C0603")
      (libsource (lib "eagle-import") (part "C-EUC0603"))
    )
    (comp (ref "C18")
      (value "10n")
      (footprint "eagle-import:C0603")
      (libsource (lib "eagle-import") (part "C-EUC0603"))
    )
    (comp (ref "C19")
      (value "1n")
      (footprint "eagle-import:C0603")
      (libsource (lib "eagle-import") (part "C-EUC0603"))
    )
    (comp (ref "C20")
      (value "1n")
      (footprint "eagle-import:C0603")
      (libsource (lib "eagle-import") (part "C-EUC0603"))
    )
    (comp (ref "D1")
      (value "RBR1L30ADDTE25")
      (footprint "eagle-import:SMA_DO-214AC")
      (libsource (lib "eagle-import") (part "SCHOTTKY_DIODESMA"))
    )
    (comp (ref "D2")
      (value "RBR1L30ADDTE25")
      (footprint "eagle-import:SMA_DO-214AC")
      (libsource (lib "eagle-import") (part "SCHOTTKY_DIODESMA"))
    )
    (comp (ref "P1")
      (value "M-2X10-DIL-100")
      (footprint "eagle-import:DIL-100-2X10")
      (libsource (lib "eagle-import") (part "M-2X10-DIL-100"))
    )
    (comp (ref "P2")
      (value "M-2X10-DIL-100")
      (footprint "eagle-import:DIL-100-2X10")
      (libsource (lib "eagle-import") (part "M-2X10-DIL-100"))
    )
    (comp (ref "R1")
      (value "560k/2W/500V")
      (footprint "eagle-import:SMV1_SMF2")
      (libsource (lib "eagle-import") (part "R-EU_SMF2"))
    )
    (comp (ref "R2")
      (value "560k/2W/500V")
      (footprint "eagle-import:SMV1_SMF2")
      (libsource (lib "eagle-import") (part "R-EU_SMF2"))
    )
    (comp (ref "R3")
      (value "560k/2W/500V")
      (footprint "eagle-import:SMV1_SMF2")
      (libsource (lib "eagle-import") (part "R-EU_SMF2"))
    )
    (comp (ref "R4")
      (value "560k/2W/500V")
      (footprint "eagle-import:SMV1_SMF2")
      (libsource (lib "eagle-import") (part "R-EU_SMF2"))
    )
    (comp (ref "R5")
      (value "4k7")
      (footprint "eagle-import:R0603")
      (libsource (lib "eagle-import") (part "R-EUR0603"))
    )
    (comp (ref "R6")
      (value "560k/2W/500V")
      (footprint "eagle-import:SMV1_SMF2")
      (libsource (lib "eagle-import") (part "R-EU_SMF2"))
    )
    (comp (ref "R7")
      (value "4k7")
      (footprint "eagle-import:R0603")
      (libsource (lib "eagle-import") (part "R-EUR0603"))
    )
    (comp (ref "R8")
      (value "560k/2W/500V")
      (footprint "eagle-import:SMV1_SMF2")
      (libsource (lib "eagle-import") (part "R-EU_SMF2"))
    )
    (comp (ref "R9")
      (value "100R")
      (footprint "eagle-import:R0603")
      (libsource (lib "eagle-import") (part "R-EUR0603"))
    )
    (comp (ref "R10")
      (value "100R")
      (footprint "eagle-import:R0603")
      (libsource (lib "eagle-import") (part "R-EUR0603"))
    )
    (comp (ref "R11")
      (value "100R")
      (footprint "eagle-import:R0603")
      (libsource (lib "eagle-import") (part "R-EUR0603"))
    )
    (comp (ref "R12")
      (value "100R")
      (footprint "eagle-import:R0603")
      (libsource (lib "eagle-import") (part "R-EUR0603"))
    )
    (comp (ref "R13")
      (value "100R")
      (footprint "eagle-import:R0603")
      (libsource (lib "eagle-import") (part "R-EUR0603"))
    )
    (comp (ref "R14")
      (value "100R")
      (footprint "eagle-import:R0603")
      (libsource (lib "eagle-import") (part "R-EUR0603"))
    )
    (comp (ref "R15")
      (value "3k3")
      (footprint "eagle-import:R0603")
      (libsource (lib "eagle-import") (part "R-EUR0603"))
    )
    (comp (ref "R16")
      (value "100R")
      (footprint "eagle-import:R0603")
      (libsource (lib "eagle-import") (part "R-EUR0603"))
    )
    (comp (ref "R17")
      (value "100R")
      (footprint "eagle-import:R0603")
      (libsource (lib "eagle-import") (part "R-EUR0603"))
    )
    (comp (ref "R18")
      (value "4k7")
      (footprint "eagle-import:R0603")
      (libsource (lib "eagle-import") (part "R-EUR0603"))
    )
    (comp (ref "R19")
      (value "4k7")
      (footprint "eagle-import:R0603")
      (libsource (lib "eagle-import") (part "R-EUR0603"))
    )
    (comp (ref "R20")
      (value "100R")
      (footprint "eagle-import:R0603")
      (libsource (lib "eagle-import") (part "R-EUR0603"))
    )
    (comp (ref "R21")
      (value "100R")
      (footprint "eagle-import:R0603")
      (libsource (lib "eagle-import") (part "R-EUR0603"))
    )
    (comp (ref "R22")
      (value "100R")
      (footprint "eagle-import:R0603")
      (libsource (lib "eagle-import") (part "R-EUR0603"))
    )
    (comp (ref "R23")
      (value "100R")
      (footprint "eagle-import:R0603")
      (libsource (lib "eagle-import") (part "R-EUR0603"))
    )
    (comp (ref "R24")
      (value "100R")
      (footprint "eagle-import:R0603")
      (libsource (lib "eagle-import") (part "R-EUR0603"))
    )
    (comp (ref "R25")
      (value "DNF")
      (footprint "eagle-import:R0603")
      (libsource (lib "eagle-import") (part "R-EUR0603"))
    )
    (comp (ref "R26")
      (value "100R")
      (footprint "eagle-import:R0603")
      (libsource (lib "eagle-import") (part "R-EUR0603"))
    )
    (comp (ref "R27")
      (value "DNF")
      (footprint "eagle-import:R0603")
      (libsource (lib "eagle-import") (part "R-EUR0603"))
    )
    (comp (ref "R28")
      (value "4k7")
      (footprint "eagle-import:R0603")
      (libsource (lib "eagle-import") (part "R-EUR0603"))
    )
    (comp (ref "R29")
      (value "4k7")
      (footprint "eagle-import:R0603")
      (libsource (lib "eagle-import") (part "R-EUR0603"))
    )
    (comp (ref "R30")
      (value "4k7")
      (footprint "eagle-import:R0603")
      (libsource (lib "eagle-import") (part "R-EUR0603"))
    )
    (comp (ref "R31")
      (value "4k7")
      (footprint "eagle-import:R0603")
      (libsource (lib "eagle-import") (part "R-EUR0603"))
    )
    (comp (ref "U1")
      (value "ADC121S101-Q")
      (footprint "eagle-import:SOT23-6")
      (libsource (lib "eagle-import") (part "ADC121S101-Q"))
    )
    (comp (ref "U2")
      (value "SI8641AB-B-IS1R")
      (footprint "eagle-import:SO16")
      (libsource (lib "eagle-import") (part "SI8641SO16"))
    )
    (comp (ref "U3")
      (value "SI8641AB-B-IS1R")
      (footprint "eagle-import:SO16")
      (libsource (lib "eagle-import") (part "SI8641SO16"))
    )
  )
  (nets
    (net (code "1") (name "+4V") (class "Default")
      (node (ref "C44") (pin "1") (pinfunction "1_1") (pintype "passive"))
      (node (ref "C45") (pin "1") (pinfunction "1_1") (pintype "passive"))
      (node (ref "C46") (pin "1") (pinfunction "1_1") (pintype "passive"))
      (node (ref "C47") (pin "1") (pinfunction "1_1") (pintype "passive"))
      (node (ref "C48") (pin "1") (pinfunction "1_1") (pintype "passive"))
      (node (ref "L2") (pin "2") (pinfunction "2_2") (pintype "passive"))
      (node (ref "X10") (pin "2") (pinfunction "2_2") (pintype "passive"))
    )
    (net (code "2") (name "+5V") (class "Default")
      (node (ref "C1") (pin "1") (pinfunction "1_1") (pintype "passive"))
      (node (ref "C10") (pin "1") (pinfunction "1_1") (pintype "passive"))
      (node (ref "C13") (pin "1") (pinfunction "1_1") (pintype "passive"))
      (node (ref "C15") (pin "1") (pinfunction "1_1") (pintype "passive"))
      (node (ref "C17") (pin "1") (pinfunction "1_1") (pintype "passive"))
      (node (ref "C19") (pin "1") (pinfunction "1_1") (pintype "passive"))
      (node (ref "C4") (pin "1") (pinfunction "1_1") (pintype "passive"))
      (node (ref "C49") (pin "1") (pinfunction "1_1") (pintype "passive"))
      (node (ref "C50") (pin "1") (pinfunction "1_1") (pintype "passive"))
      (node (ref "C51") (pin "1") (pinfunction "1_1") (pintype "passive"))
      (node (ref "C52") (pin "1") (pinfunction "1_1") (pintype "passive"))
      (node (ref "C65") (pin "1") (pinfunction "1_1") (pintype "passive"))
      (node (ref "C67") (pin "1") (pinfunction "1_1") (pintype "passive"))
      (node (ref "C68") (pin "1") (pinfunction "1_1") (pintype "passive"))
      (node (ref "C69") (pin "1") (pinfunction "1_1") (pintype "passive"))
      (node (ref "C7") (pin "1") (pinfunction "1_1") (pintype "passive"))
      (node (ref "C70") (pin "1") (pinfunction "1_1") (pintype "passive"))
      (node (ref "C71") (pin "1") (pinfunction "1_1") (pintype "passive"))
      (node (ref "C72") (pin "1") (pinfunction "1_1") (pintype "passive"))
      (node (ref "C73") (pin "1") (pinfunction "1_1") (pintype "passive"))
      (node (ref "C75") (pin "1") (pinfunction "1_1") (pintype "passive"))
      (node (ref "C76") (pin "1") (pinfunction "1_1") (pintype "passive"))
      (node (ref "C77") (pin "1") (pinfunction "1_1") (pintype "passive"))
      (node (ref "C78") (pin "1") (pinfunction "1_1") (pintype "passive"))
      (node (ref "C83") (pin "1") (pinfunction "1_1") (pintype "passive"))
      (node (ref "C84") (pin "1") (pinfunction "1_1") (pintype "passive"))
      (node (ref "C85") (pin "1") (pinfunction "1_1") (pintype "passive"))
      (node (ref "C86") (pin "1") (pinfunction "1_1") (pintype "passive"))
      (node (ref "C88") (pin "1") (pinfunction "1_1") (pintype "passive"))
      (node (ref "C89") (pin "1") (pinfunction "1_1") (pintype "passive"))
      (node (ref "C90") (pin "1") (pinfunction "1_1") (pintype "passive"))
      (node (ref "C91") (pin "1") (pinfunction "1_1") (pintype "passive"))
      (node (ref "C92") (pin "1") (pinfunction "1_1") (pintype "passive"))
      (node (ref "C93") (pin "1") (pinfunction "1_1") (pintype "passive"))
      (node (ref "C94") (pin "1") (pinfunction "1_1") (pintype "passive"))
      (node (ref "C95") (pin "1") (pinfunction "1_1") (pintype "passive"))
      (node (ref "IC1") (pin "5") (pinfunction "V+_5") (pintype "power_in"))
      (node (ref "IC2") (pin "5") (pinfunction "V+_5") (pintype "power_in"))
      (node (ref "P3") (pin "10") (pinfunction "10_10") (pintype "passive"))
      (node (ref "P3") (pin "2") (pinfunction "2_2") (pintype "passive"))
      (node (ref "P3") (pin "4") (pinfunction "4_4") (pintype "passive"))
      (node (ref "P3") (pin "6") (pinfunction "6_6") (pintype "passive"))
      (node (ref "P3") (pin "8") (pinfunction "8_8") (pintype "passive"))
      (node (ref "R19") (pin "2") (pinfunction "2_2") (pintype "passive"))
      (node (ref "R43") (pin "2") (pinfunction "2_2") (pintype "passive"))
      (node (ref "R52") (pin "2") (pinfunction "2_2") (pintype "passive"))
      (node (ref "R7") (pin "2") (pinfunction "2_2") (pintype "passive"))
      (node (ref "U2") (pin "1") (pinfunction "VDD1_1") (pintype "power_in"))
      (node (ref "U3") (pin "1") (pinfunction "VDD1_1") (pintype "power_in"))
      (node (ref "U4") (pin "1") (pinfunction "VA_1") (pintype "power_in"))
      (node (ref "U5") (pin "10") (pinfunction "VCC_10") (pintype "bidirectional"))
      (node (ref "U6") (pin "1") (pinfunction "VA_1") (pintype "power_in"))
      (node (ref "U7") (pin "10") (pinfunction "VCC_10") (pintype "bidirectional"))
      (node (ref "VR3") (pin "+V") (pinfunction "V+_+V") (pintype "passive"))
      (node (ref "X11") (pin "2") (pinfunction "2_2") (pintype "passive"))
    )
    (net (code "3") (name "+12V") (class "Default")
      (node (ref "C40") (pin "1") (pinfunction "1_1") (pintype "passive"))
      (node (ref "C41") (pin "1") (pinfunction "1_1") (pintype "passive"))
      (node (ref "C42") (pin "1") (pinfunction "1_1") (pintype "passive"))
      (node (ref "C43") (pin "1") (pinfunction "1_1") (pintype "passive"))
      (node (ref "C53") (pin "1") (pinfunction "1_1") (pintype "passive"))
      (node (ref "C54") (pin "1") (pinfunction "1_1") (pintype "passive"))
      (node (ref "C55") (pin "1") (pinfunction "1_1") (pintype "passive"))
      (node (ref "C56") (pin "1") (pinfunction "1_1") (pintype "passive"))
      (node (ref "P3") (pin "1") (pinfunction "1_1") (pintype "passive"))
      (node (ref "P3") (pin "3") (pinfunction "3_3") (pintype "passive"))
      (node (ref "P3") (pin "5") (pinfunction "5_5") (pintype "passive"))
      (node (ref "P3") (pin "7") (pinfunction "7_7") (pintype "passive"))
      (node (ref "P3") (pin "9") (pinfunction "9_9") (pintype "passive"))
      (node (ref "R33") (pin "2") (pinfunction "2_2") (pintype "passive"))
      (node (ref "VR2") (pin "3") (pinfunction "VIN_3") (pintype "bidirectional"))
      (node (ref "VR4") (pin "+V") (pinfunction "V+_+V") (pintype "passive"))
      (node (ref "X12") (pin "2") (pinfunction "2_2") (pintype "passive"))
      (node (ref "X13") (pin "2") (pinfunction "2_2") (pintype "passive"))
    )
    (net (code "4") (name "AC{slash}L") (class "Default")
      (node (ref "C22") (pin "1") (pinfunction "1_1") (pintype "passive"))
      (node (ref "C24") (pin "1") (pinfunction "1_1") (pintype "passive"))
      (node (ref "L1") (pin "3") (pinfunction "2_3") (pintype "passive"))
      (node (ref "VR1") (pin "AC/L") (pinfunction "AC/L_AC/L") (pintype "passive"))
      (node (ref "VR3") (pin "AC/L") (pinfunction "AC/L_AC/L") (pintype "passive"))
      (node (ref "VR4") (pin "AC/L") (pinfunction "AC/L_AC/L") (pintype "passive"))
      (node (ref "X3") (pin "3") (pinfunction "3_3") (pintype "passive"))
      (node (ref "X5") (pin "3") (pinfunction "3_3") (pintype "passive"))
      (node (ref "X6") (pin "3") (pinfunction "3_3") (pintype "passive"))
    )
    (net (code "5") (name "AC{slash}N") (class "Default")
      (node (ref "C24") (pin "2") (pinfunction "2_2") (pintype "passive"))
      (node (ref "C26") (pin "2") (pinfunction "2_2") (pintype "passive"))
      (node (ref "L1") (pin "2") (pinfunction "3_2") (pintype "passive"))
      (node (ref "VR1") (pin "AC/N") (pinfunction "AC/N_AC/N") (pintype "passive"))
      (node (ref "VR3") (pin "AC/N") (pinfunction "AC/N_AC/N") (pintype "passive"))
      (node (ref "VR4") (pin "AC/N") (pinfunction "AC/N_AC/N") (pintype "passive"))
      (node (ref "X3") (pin "1") (pinfunction "1_1") (pintype "passive"))
      (node (ref "X5") (pin "1") (pinfunction "1_1") (pintype "passive"))
      (node (ref "X6") (pin "1") (pinfunction "1_1") (pintype "passive"))
    )
    (net (code "6") (name "EARTH") (class "Default")
      (node (ref "C21") (pin "2") (pinfunction "2_2") (pintype "passive"))
      (node (ref "C22") (pin "2") (pinfunction "2_2") (pintype "passive"))
      (node (ref "C25") (pin "1") (pinfunction "1_1") (pintype "passive"))
      (node (ref "C26") (pin "1") (pinfunction "1_1") (pintype "passive"))
      (node (ref "X1") (pin "2") (pinfunction "2_2") (pintype "passive"))
      (node (ref "X3") (pin "2") (pinfunction "2_2") (pintype "passive"))
      (node (ref "X5") (pin "2") (pinfunction "2_2") (pintype "passive"))
      (node (ref "X6") (pin "2") (pinfunction "2_2") (pintype "passive"))
    )
    (net (code "7") (name "GND") (class "Default")
      (node (ref "C1") (pin "2") (pinfunction "2_2") (pintype "passive"))
      (node (ref "C10") (pin "2") (pinfunction "2_2") (pintype "passive"))
      (node (ref "C13") (pin "2") (pinfunction "2_2") (pintype "passive"))
      (node (ref "C15") (pin "2") (pinfunction "2_2") (pintype "passive"))
      (node (ref "C17") (pin "2") (pinfunction "2_2") (pintype "passive"))
      (node (ref "C19") (pin "2") (pinfunction "2_2") (pintype "passive"))
      (node (ref "C4") (pin "2") (pinfunction "2_2") (pintype "passive"))
      (node (ref "C40") (pin "2") (pinfunction "2_2") (pintype "passive"))
      (node (ref "C41") (pin "2") (pinfunction "2_2") (pintype "passive"))
      (node (ref "C42") (pin "2") (pinfunction "2_2") (pintype "passive"))
      (node (ref "C43") (pin "2") (pinfunction "2_2") (pintype "passive"))
      (node (ref "C44") (pin "2") (pinfunction "2_2") (pintype "passive"))
      (node (ref "C45") (pin "2") (pinfunction "2_2") (pintype "passive"))
      (node (ref "C46") (pin "2") (pinfunction "2_2") (pintype "passive"))
      (node (ref "C47") (pin "2") (pinfunction "2_2") (pintype "passive"))
      (node (ref "C48") (pin "2") (pinfunction "2_2") (pintype "passive"))
      (node (ref "C49") (pin "2") (pinfunction "2_2") (pintype "passive"))
      (node (ref "C50") (pin "2") (pinfunction "2_2") (pintype "passive"))
      (node (ref "C51") (pin "2") (pinfunction "2_2") (pintype "passive"))
      (node (ref "C52") (pin "2") (pinfunction "2_2") (pintype "passive"))
      (node (ref "C53") (pin "2") (pinfunction "2_2") (pintype "passive"))
      (node (ref "C54") (pin "2") (pinfunction "2_2") (pintype "passive"))
      (node (ref "C55") (pin "2") (pinfunction "2_2") (pintype "passive"))
      (node (ref "C56") (pin "2") (pinfunction "2_2") (pintype "passive"))
      (node (ref "C65") (pin "2") (pinfunction "2_2") (pintype "passive"))
      (node (ref "C67") (pin "2") (pinfunction "2_2") (pintype "passive"))
      (node (ref "C68") (pin "2") (pinfunction "2_2") (pintype "passive"))
      (node (ref "C69") (pin "2") (pinfunction "2_2") (pintype "passive"))
      (node (ref "C7") (pin "2") (pinfunction "2_2") (pintype "passive"))
      (node (ref "C70") (pin "2") (pinfunction "2_2") (pintype "passive"))
      (node (ref "C71") (pin "2") (pinfunction "2_2") (pintype "passive"))
      (node (ref "C72") (pin "2") (pinfunction "2_2") (pintype "passive"))
      (node (ref "C73") (pin "2") (pinfunction "2_2") (pintype "passive"))
      (node (ref "C75") (pin "2") (pinfunction "2_2") (pintype "passive"))
      (node (ref "C76") (pin "2") (pinfunction "2_2") (pintype "passive"))
      (node (ref "C77") (pin "2") (pinfunction "2_2") (pintype "passive"))
      (node (ref "C78") (pin "2") (pinfunction "2_2") (pintype "passive"))
      (node (ref "C80") (pin "2") (pinfunction "2_2") (pintype "passive"))
      (node (ref "C83") (pin "2") (pinfunction "2_2") (pintype "passive"))
      (node (ref "C84") (pin "2") (pinfunction "2_2") (pintype "passive"))
      (node (ref "C85") (pin "2") (pinfunction "2_2") (pintype "passive"))
      (node (ref "C86") (pin "2") (pinfunction "2_2") (pintype "passive"))
      (node (ref "C88") (pin "2") (pinfunction "2_2") (pintype "passive"))
      (node (ref "C89") (pin "2") (pinfunction "2_2") (pintype "passive"))
      (node (ref "C90") (pin "2") (pinfunction "2_2") (pintype "passive"))
      (node (ref "C91") (pin "2") (pinfunction "2_2") (pintype "passive"))
      (node (ref "C92") (pin "2") (pinfunction "2_2") (pintype "passive"))
      (node (ref "C93") (pin "2") (pinfunction "2_2") (pintype "passive"))
      (node (ref "C94") (pin "2") (pinfunction "2_2") (pintype "passive"))
      (node (ref "C95") (pin "2") (pinfunction "2_2") (pintype "passive"))
      (node (ref "C96") (pin "2") (pinfunction "2_2") (pintype "passive"))
      (node (ref "IC1") (pin "2") (pinfunction "V-_2") (pintype "power_in"))
      (node (ref "IC2") (pin "2") (pinfunction "V-_2") (pintype "power_in"))
      (node (ref "P1") (pin "10") (pinfunction "10_10") (pintype "passive"))
      (node (ref "P1") (pin "11") (pinfunction "11_11") (pintype "passive"))
      (node (ref "P1") (pin "12") (pinfunction "12_12") (pintype "passive"))
      (node (ref "P1") (pin "13") (pinfunction "13_13") (pintype "passive"))
      (node (ref "P1") (pin "14") (pinfunction "14_14") (pintype "passive"))
      (node (ref "P1") (pin "15") (pinfunction "15_15") (pintype "passive"))
      (node (ref "P1") (pin "16") (pinfunction "16_16") (pintype "passive"))
      (node (ref "P1") (pin "17") (pinfunction "17_17") (pintype "passive"))
      (node (ref "P1") (pin "18") (pinfunction "18_18") (pintype "passive"))
      (node (ref "P1") (pin "19") (pinfunction "19_19") (pintype "passive"))
      (node (ref "P1") (pin "20") (pinfunction "20_20") (pintype "passive"))
      (node (ref "P1") (pin "9") (pinfunction "9_9") (pintype "passive"))
      (node (ref "P3") (pin "11") (pinfunction "11_11") (pintype "passive"))
      (node (ref "P3") (pin "12") (pinfunction "12_12") (pintype "passive"))
      (node (ref "P3") (pin "13") (pinfunction "13_13") (pintype "passive"))
      (node (ref "P3") (pin "14") (pinfunction "14_14") (pintype "passive"))
      (node (ref "P3") (pin "15") (pinfunction "15_15") (pintype "passive"))
      (node (ref "P3") (pin "16") (pinfunction "16_16") (pintype "passive"))
      (node (ref "P3") (pin "17") (pinfunction "17_17") (pintype "passive"))
      (node (ref "P3") (pin "18") (pinfunction "18_18") (pintype "passive"))
      (node (ref "P3") (pin "19") (pinfunction "19_19") (pintype "passive"))
      (node (ref "P3") (pin "20") (pinfunction "20_20") (pintype "passive"))
      (node (ref "R28") (pin "1") (pinfunction "1_1") (pintype "passive"))
      (node (ref "R29") (pin "1") (pinfunction "1_1") (pintype "passive"))
      (node (ref "R35") (pin "1") (pinfunction "1_1") (pintype "passive"))
      (node (ref "R36") (pin "1") (pinfunction "1_1") (pintype "passive"))
      (node (ref "R47") (pin "1") (pinfunction "1_1") (pintype "passive"))
      (node (ref "R48") (pin "1") (pinfunction "1_1") (pintype "passive"))
      (node (ref "R55") (pin "1") (pinfunction "1_1") (pintype "passive"))
      (node (ref "R56") (pin "1") (pinfunction "1_1") (pintype "passive"))
      (node (ref "U2") (pin "2") (pinfunction "GND1_2") (pintype "power_in"))
      (node (ref "U2") (pin "8") (pinfunction "GND1_8") (pintype "power_in"))
      (node (ref "U3") (pin "2") (pinfunction "GND1_2") (pintype "power_in"))
      (node (ref "U3") (pin "8") (pinfunction "GND1_8") (pintype "power_in"))
      (node (ref "U4") (pin "2") (pinfunction "GND_2") (pintype "power_in"))
      (node (ref "U5") (pin "11") (pinfunction "GND_11") (pintype "bidirectional"))
      (node (ref "U5") (pin "14") (pinfunction "GND_14") (pintype "bidirectional"))
      (node (ref "U5") (pin "15") (pinfunction "GND_15") (pintype "bidirectional"))
      (node (ref "U6") (pin "2") (pinfunction "GND_2") (pintype "power_in"))
      (node (ref "U7") (pin "11") (pinfunction "GND_11") (pintype "bidirectional"))
      (node (ref "U7") (pin "14") (pinfunction "GND_14") (pintype "bidirectional"))
      (node (ref "U7") (pin "15") (pinfunction "GND_15") (pintype "bidirectional"))
      (node (ref "VR2") (pin "1") (pinfunction "GND_1") (pintype "bidirectional"))
      (node (ref "VR3") (pin "-V") (pinfunction "V-_-V") (pintype "passive"))
      (node (ref "VR4") (pin "-V") (pinfunction "V-_-V") (pintype "passive"))
      (node (ref "X10") (pin "1") (pinfunction "1_1") (pintype "passive"))
      (node (ref "X11") (pin "1") (pinfunction "1_1") (pintype "passive"))
      (node (ref "X12") (pin "1") (pinfunction "1_1") (pintype "passive"))
      (node (ref "X13") (pin "1") (pinfunction "1_1") (pintype "passive"))
    )
    (net (code "8") (name "GRID_CURR_AMP") (class "Default")
      (node (ref "R44") (pin "1") (pinfunction "1_1") (pintype "passive"))
      (node (ref "R57") (pin "1") (pinfunction "1_1") (pintype "passive"))
      (node (ref "U4") (pin "3") (pinfunction "VIN_3") (pintype "input"))
    )
    (net (code "9") (name "GRID_CURR_FAULT") (class "Default")
      (node (ref "TP2") (pin "TP") (pinfunction "TP_TP") (pintype "input"))
      (node (ref "U5") (pin "9") (pinfunction "~{FAULTB}_9") (pintype "bidirectional"))
    )
    (net (code "10") (name "GRID_CURR_OUT") (class "Default")
      (node (ref "IC1") (pin "1") (pinfunction "+IN_1") (pintype "input"))
      (node (ref "R44") (pin "2") (pinfunction "2_2") (pintype "passive"))
      (node (ref "U5") (pin "12") (pinfunction "VOUT_12") (pintype "bidirectional"))
    )
    (net (code "11") (name "Net-(C39-Pad1)") (class "Default")
      (node (ref "C39") (pin "1") (pinfunction "1_1") (pintype "passive"))
      (node (ref "R32") (pin "2") (pinfunction "2_2") (pintype "passive"))
    )
    (net (code "12") (name "Net-(C57-Pad2)") (class "Default")
      (node (ref "C57") (pin "2") (pinfunction "2_2") (pintype "passive"))
      (node (ref "C58") (pin "2") (pinfunction "2_2") (pintype "passive"))
      (node (ref "C59") (pin "2") (pinfunction "2_2") (pintype "passive"))
      (node (ref "C61") (pin "1") (pinfunction "1_1") (pintype "passive"))
      (node (ref "C62") (pin "1") (pinfunction "1_1") (pintype "passive"))
      (node (ref "C63") (pin "1") (pinfunction "1_1") (pintype "passive"))
      (node (ref "R37") (pin "1") (pinfunction "1_1") (pintype "passive"))
      (node (ref "R39") (pin "2") (pinfunction "2_2") (pintype "passive"))
    )
    (net (code "13") (name "Net-(C60--)") (class "Default")
      (node (ref "C60") (pin "-VE") (pinfunction "-_-VE") (pintype "passive"))
      (node (ref "C64") (pin "+VE") (pinfunction "+_+VE") (pintype "passive"))
      (node (ref "R38") (pin "1") (pinfunction "1_1") (pintype "passive"))
      (node (ref "R40") (pin "2") (pinfunction "2_2") (pintype "passive"))
    )
    (net (code "14") (name "Net-(C64--)") (class "Default")
      (node (ref "C64") (pin "-VE") (pinfunction "-_-VE") (pintype "passive"))
      (node (ref "C66") (pin "+VE") (pinfunction "+_+VE") (pintype "passive"))
      (node (ref "R40") (pin "1") (pinfunction "1_1") (pintype "passive"))
      (node (ref "R41") (pin "2") (pinfunction "2_2") (pintype "passive"))
    )
    (net (code "15") (name "Net-(C66--)") (class "Default")
      (node (ref "C66") (pin "-VE") (pinfunction "-_-VE") (pintype "passive"))
      (node (ref "C74") (pin "+VE") (pinfunction "+_+VE") (pintype "passive"))
      (node (ref "R41") (pin "1") (pinfunction "1_1") (pintype "passive"))
      (node (ref "R42") (pin "2") (pinfunction "2_2") (pintype "passive"))
    )
    (net (code "16") (name "Net-(C74--)") (class "Default")
      (node (ref "C74") (pin "-VE") (pinfunction "-_-VE") (pintype "passive"))
      (node (ref "C79") (pin "+VE") (pinfunction "+_+VE") (pintype "passive"))
      (node (ref "R42") (pin "1") (pinfunction "1_1") (pintype "passive"))
      (node (ref "R45") (pin "2") (pinfunction "2_2") (pintype "passive"))
    )
    (net (code "17") (name "Net-(C79--)") (class "Default")
      (node (ref "C79") (pin "-VE") (pinfunction "-_-VE") (pintype "passive"))
      (node (ref "C81") (pin "+VE") (pinfunction "+_+VE") (pintype "passive"))
      (node (ref "R45") (pin "1") (pinfunction "1_1") (pintype "passive"))
      (node (ref "R49") (pin "2") (pinfunction "2_2") (pintype "passive"))
    )
    (net (code "18") (name "Net-(C81--)") (class "Default")
      (node (ref "C81") (pin "-VE") (pinfunction "-_-VE") (pintype "passive"))
      (node (ref "C82") (pin "+VE") (pinfunction "+_+VE") (pintype "passive"))
      (node (ref "R49") (pin "1") (pinfunction "1_1") (pintype "passive"))
      (node (ref "R50") (pin "2") (pinfunction "2_2") (pintype "passive"))
    )
    (net (code "19") (name "Net-(D1-ANODE)") (class "Default")
      (node (ref "D1") (pin "A") (pinfunction "ANODE_A") (pintype "bidirectional"))
      (node (ref "D2") (pin "C") (pinfunction "CATHODE_C") (pintype "bidirectional"))
      (node (ref "R15") (pin "2") (pinfunction "2_2") (pintype "passive"))
      (node (ref "R8") (pin "1") (pinfunction "1_1") (pintype "passive"))
      (node (ref "U1") (pin "3") (pinfunction "VIN_3") (pintype "input"))
    )
    (net (code "20") (name "Net-(D3-PadA)") (class "Default")
      (node (ref "D3") (pin "A") (pinfunction "A_A") (pintype "passive"))
      (node (ref "D5") (pin "C") (pinfunction "C_C") (pintype "passive"))
      (node (ref "X4") (pin "2") (pinfunction "2_2") (pintype "passive"))
    )
    (net (code "21") (name "Net-(D4-PadA)") (class "Default")
      (node (ref "D4") (pin "A") (pinfunction "A_A") (pintype "passive"))
      (node (ref "D6") (pin "C") (pinfunction "C_C") (pintype "passive"))
      (node (ref "X4") (pin "1") (pinfunction "1_1") (pintype "passive"))
    )
    (net (code "22") (name "Net-(D7-PadA)") (class "Default")
      (node (ref "D7") (pin "A") (pinfunction "A_A") (pintype "passive"))
      (node (ref "D9") (pin "C") (pinfunction "C_C") (pintype "passive"))
      (node (ref "X8") (pin "2") (pinfunction "2_2") (pintype "passive"))
    )
    (net (code "23") (name "Net-(D10-PadC)") (class "Default")
      (node (ref "D10") (pin "C") (pinfunction "C_C") (pintype "passive"))
      (node (ref "D8") (pin "A") (pinfunction "A_A") (pintype "passive"))
      (node (ref "X8") (pin "1") (pinfunction "1_1") (pintype "passive"))
    )
    (net (code "24") (name "Net-(D11-ANODE)") (class "Default")
      (node (ref "D11") (pin "3") (pinfunction "ANODE_3") (pintype "bidirectional"))
      (node (ref "D13") (pin "1") (pinfunction "CATHODE_1") (pintype "bidirectional"))
    )
    (net (code "25") (name "Net-(D12-ANODE)") (class "Default")
      (node (ref "D12") (pin "3") (pinfunction "ANODE_3") (pintype "bidirectional"))
      (node (ref "D14") (pin "1") (pinfunction "CATHODE_1") (pintype "bidirectional"))
    )
    (net (code "26") (name "Net-(D13-ANODE)") (class "Default")
      (node (ref "D13") (pin "3") (pinfunction "ANODE_3") (pintype "bidirectional"))
      (node (ref "D15") (pin "1") (pinfunction "CATHODE_1") (pintype "bidirectional"))
      (node (ref "X15") (pin "1") (pinfunction "1_1") (pintype "passive"))
      (node (ref "X15") (pin "2") (pinfunction "2_2") (pintype "passive"))
    )
    (net (code "27") (name "Net-(D14-ANODE)") (class "Default")
      (node (ref "D14") (pin "3") (pinfunction "ANODE_3") (pintype "bidirectional"))
      (node (ref "D16") (pin "1") (pinfunction "CATHODE_1") (pintype "bidirectional"))
      (node (ref "X16") (pin "1") (pinfunction "1_1") (pintype "passive"))
      (node (ref "X16") (pin "2") (pinfunction "2_2") (pintype "passive"))
    )
    (net (code "28") (name "Net-(D15-ANODE)") (class "Default")
      (node (ref "D15") (pin "3") (pinfunction "ANODE_3") (pintype "bidirectional"))
      (node (ref "D17") (pin "1") (pinfunction "CATHODE_1") (pintype "bidirectional"))
    )
    (net (code "29") (name "Net-(D16-ANODE)") (class "Default")
      (node (ref "D16") (pin "3") (pinfunction "ANODE_3") (pintype "bidirectional"))
      (node (ref "D18") (pin "1") (pinfunction "CATHODE_1") (pintype "bidirectional"))
    )
    (net (code "30") (name "Net-(IC1--IN)") (class "Default")
      (node (ref "IC1") (pin "3") (pinfunction "-IN_3") (pintype "input"))
      (node (ref "R46") (pin "2") (pinfunction "2_2") (pintype "passive"))
      (node (ref "R48") (pin "2") (pinfunction "2_2") (pintype "passive"))
    )
    (net (code "31") (name "Net-(IC1-OUT)") (class "Default")
      (node (ref "IC1") (pin "4") (pinfunction "OUT_4") (pintype "output"))
      (node (ref "R46") (pin "1") (pinfunction "1_1") (pintype "passive"))
      (node (ref "R57") (pin "2") (pinfunction "2_2") (pintype "passive"))
    )
    (net (code "32") (name "Net-(IC2--IN)") (class "Default")
      (node (ref "IC2") (pin "3") (pinfunction "-IN_3") (pintype "input"))
      (node (ref "R54") (pin "2") (pinfunction "2_2") (pintype "passive"))
      (node (ref "R55") (pin "2") (pinfunction "2_2") (pintype "passive"))
    )
    (net (code "33") (name "Net-(IC2-OUT)") (class "Default")
      (node (ref "IC2") (pin "4") (pinfunction "OUT_4") (pintype "output"))
      (node (ref "R51") (pin "2") (pinfunction "2_2") (pintype "passive"))
      (node (ref "R54") (pin "1") (pinfunction "1_1") (pintype "passive"))
    )
    (net (code "34") (name "Net-(L1-1)") (class "Default")
      (node (ref "C21") (pin "1") (pinfunction "1_1") (pintype "passive"))
      (node (ref "C23") (pin "1") (pinfunction "1_1") (pintype "passive"))
      (node (ref "L1") (pin "4") (pinfunction "1_4") (pintype "passive"))
      (node (ref "X1") (pin "1") (pinfunction "1_1") (pintype "passive"))
    )
    (net (code "35") (name "Net-(L1-4)") (class "Default")
      (node (ref "C23") (pin "2") (pinfunction "2_2") (pintype "passive"))
      (node (ref "C25") (pin "2") (pinfunction "2_2") (pintype "passive"))
      (node (ref "L1") (pin "1") (pinfunction "4_1") (pintype "passive"))
      (node (ref "X1") (pin "3") (pinfunction "3_3") (pintype "passive"))
    )
    (net (code "36") (name "Net-(R1-Pad2)") (class "Default")
      (node (ref "R1") (pin "2") (pinfunction "2_2") (pintype "passive"))
      (node (ref "R2") (pin "2") (pinfunction "2_2") (pintype "passive"))
    )
    (net (code "37") (name "Net-(R2-Pad1)") (class "Default")
      (node (ref "R2") (pin "1") (pinfunction "1_1") (pintype "passive"))
      (node (ref "R3") (pin "1") (pinfunction "1_1") (pintype "passive"))
    )
    (net (code "38") (name "Net-(R3-Pad2)") (class "Default")
      (node (ref "R3") (pin "2") (pinfunction "2_2") (pintype "passive"))
      (node (ref "R4") (pin "2") (pinfunction "2_2") (pintype "passive"))
    )
    (net (code "39") (name "Net-(R4-Pad1)") (class "Default")
      (node (ref "R4") (pin "1") (pinfunction "1_1") (pintype "passive"))
      (node (ref "R6") (pin "1") (pinfunction "1_1") (pintype "passive"))
    )
    (net (code "40") (name "Net-(R6-Pad2)") (class "Default")
      (node (ref "R6") (pin "2") (pinfunction "2_2") (pintype "passive"))
      (node (ref "R8") (pin "2") (pinfunction "2_2") (pintype "passive"))
    )
    (net (code "41") (name "Net-(R24-Pad1)") (class "Default")
      (node (ref "R24") (pin "1") (pinfunction "1_1") (pintype "passive"))
      (node (ref "R28") (pin "2") (pinfunction "2_2") (pintype "passive"))
    )
    (net (code "42") (name "Net-(R26-Pad1)") (class "Default")
      (node (ref "R26") (pin "1") (pinfunction "1_1") (pintype "passive"))
      (node (ref "R29") (pin "2") (pinfunction "2_2") (pintype "passive"))
    )
    (net (code "43") (name "Net-(U1-~{CS})") (class "Default")
      (node (ref "R10") (pin "2") (pinfunction "2_2") (pintype "passive"))
      (node (ref "U1") (pin "6") (pinfunction "~{CS}_6") (pintype "passive"))
    )
    (net (code "44") (name "Net-(U2-A1)") (class "Default")
      (node (ref "R9") (pin "2") (pinfunction "2_2") (pintype "passive"))
      (node (ref "U2") (pin "3") (pinfunction "A1_3") (pintype "bidirectional"))
    )
    (net (code "45") (name "Net-(U2-A2)") (class "Default")
      (node (ref "R11") (pin "2") (pinfunction "2_2") (pintype "passive"))
      (node (ref "U2") (pin "4") (pinfunction "A2_4") (pintype "bidirectional"))
    )
    (net (code "46") (name "Net-(U2-A3)") (class "Default")
      (node (ref "R13") (pin "2") (pinfunction "2_2") (pintype "passive"))
      (node (ref "U2") (pin "5") (pinfunction "A3_5") (pintype "bidirectional"))
    )
    (net (code "47") (name "Net-(U2-A4)") (class "Default")
      (node (ref "R16") (pin "2") (pinfunction "2_2") (pintype "passive"))
      (node (ref "U2") (pin "6") (pinfunction "A4_6") (pintype "bidirectional"))
    )
    (net (code "48") (name "Net-(U2-B1)") (class "Default")
      (node (ref "R10") (pin "1") (pinfunction "1_1") (pintype "passive"))
      (node (ref "U2") (pin "14") (pinfunction "B1_14") (pintype "bidirectional"))
    )
    (net (code "49") (name "Net-(U2-B2)") (class "Default")
      (node (ref "R12") (pin "1") (pinfunction "1_1") (pintype "passive"))
      (node (ref "U2") (pin "13") (pinfunction "B2_13") (pintype "bidirectional"))
    )
    (net (code "50") (name "Net-(U2-B3)") (class "Default")
      (node (ref "R14") (pin "1") (pinfunction "1_1") (pintype "passive"))
      (node (ref "U2") (pin "12") (pinfunction "B3_12") (pintype "bidirectional"))
    )
    (net (code "51") (name "Net-(U2-B4)") (class "Default")
      (node (ref "R17") (pin "1") (pinfunction "1_1") (pintype "passive"))
      (node (ref "U2") (pin "11") (pinfunction "B4_11") (pintype "bidirectional"))
    )
    (net (code "52") (name "Net-(U2-EN1)") (class "Default")
      (node (ref "R7") (pin "1") (pinfunction "1_1") (pintype "passive"))
      (node (ref "U2") (pin "7") (pinfunction "EN1_7") (pintype "bidirectional"))
    )
    (net (code "53") (name "Net-(U2-EN2)") (class "Default")
      (node (ref "R5") (pin "1") (pinfunction "1_1") (pintype "passive"))
      (node (ref "U2") (pin "10") (pinfunction "EN2_10") (pintype "bidirectional"))
    )
    (net (code "54") (name "Net-(U3-A1)") (class "Default")
      (node (ref "R20") (pin "2") (pinfunction "2_2") (pintype "passive"))
      (node (ref "U3") (pin "3") (pinfunction "A1_3") (pintype "bidirectional"))
    )
    (net (code "55") (name "Net-(U3-A2)") (class "Default")
      (node (ref "R22") (pin "2") (pinfunction "2_2") (pintype "passive"))
      (node (ref "U3") (pin "4") (pinfunction "A2_4") (pintype "bidirectional"))
    )
    (net (code "56") (name "Net-(U3-A3)") (class "Default")
      (node (ref "R24") (pin "2") (pinfunction "2_2") (pintype "passive"))
      (node (ref "U3") (pin "5") (pinfunction "A3_5") (pintype "bidirectional"))
    )
    (net (code "57") (name "Net-(U3-A4)") (class "Default")
      (node (ref "R26") (pin "2") (pinfunction "2_2") (pintype "passive"))
      (node (ref "U3") (pin "6") (pinfunction "A4_6") (pintype "bidirectional"))
    )
    (net (code "58") (name "Net-(U3-B1)") (class "Default")
      (node (ref "R21") (pin "1") (pinfunction "1_1") (pintype "passive"))
      (node (ref "U3") (pin "14") (pinfunction "B1_14") (pintype "bidirectional"))
    )
    (net (code "59") (name "Net-(U3-B2)") (class "Default")
      (node (ref "R23") (pin "1") (pinfunction "1_1") (pintype "passive"))
      (node (ref "U3") (pin "13") (pinfunction "B2_13") (pintype "bidirectional"))
    )
    (net (code "60") (name "Net-(U3-B3)") (class "Default")
      (node (ref "R25") (pin "1") (pinfunction "1_1") (pintype "passive"))
      (node (ref "R31") (pin "2") (pinfunction "2_2") (pintype "passive"))
      (node (ref "U3") (pin "12") (pinfunction "B3_12") (pintype "bidirectional"))
    )
    (net (code "61") (name "Net-(U3-B4)") (class "Default")
      (node (ref "R27") (pin "1") (pinfunction "1_1") (pintype "passive"))
      (node (ref "R30") (pin "2") (pinfunction "2_2") (pintype "passive"))
      (node (ref "U3") (pin "11") (pinfunction "B4_11") (pintype "bidirectional"))
    )
    (net (code "62") (name "Net-(U3-EN1)") (class "Default")
      (node (ref "R19") (pin "1") (pinfunction "1_1") (pintype "passive"))
      (node (ref "U3") (pin "7") (pinfunction "EN1_7") (pintype "bidirectional"))
    )
    (net (code "63") (name "Net-(U3-EN2)") (class "Default")
      (node (ref "R18") (pin "1") (pinfunction "1_1") (pintype "passive"))
      (node (ref "U3") (pin "10") (pinfunction "EN2_10") (pintype "bidirectional"))
    )
    (net (code "64") (name "Net-(U5-VOC)") (class "Default")
      (node (ref "R43") (pin "1") (pinfunction "1_1") (pintype "passive"))
      (node (ref "R47") (pin "2") (pinfunction "2_2") (pintype "passive"))
      (node (ref "U5") (pin "16") (pinfunction "VOC_16") (pintype "bidirectional"))
    )
    (net (code "65") (name "Net-(U5-VREF)") (class "Default")
      (node (ref "C80") (pin "1") (pinfunction "1_1") (pintype "passive"))
      (node (ref "U5") (pin "13") (pinfunction "VREF_13") (pintype "bidirectional"))
    )
    (net (code "66") (name "Net-(U7-VOC)") (class "Default")
      (node (ref "R52") (pin "1") (pinfunction "1_1") (pintype "passive"))
      (node (ref "R56") (pin "2") (pinfunction "2_2") (pintype "passive"))
      (node (ref "U7") (pin "16") (pinfunction "VOC_16") (pintype "bidirectional"))
    )
    (net (code "67") (name "Net-(U7-VREF)") (class "Default")
      (node (ref "C96") (pin "1") (pinfunction "1_1") (pintype "passive"))
      (node (ref "U7") (pin "13") (pinfunction "VREF_13") (pintype "bidirectional"))
    )
    (net (code "68") (name "Net-(VR2-BOOT)") (class "Default")
      (node (ref "R32") (pin "1") (pinfunction "1_1") (pintype "passive"))
      (node (ref "VR2") (pin "6") (pinfunction "BOOT_6") (pintype "bidirectional"))
    )
    (net (code "69") (name "Net-(VR2-EN)") (class "Default")
      (node (ref "R33") (pin "1") (pinfunction "1_1") (pintype "passive"))
      (node (ref "R35") (pin "2") (pinfunction "2_2") (pintype "passive"))
      (node (ref "VR2") (pin "5") (pinfunction "EN_5") (pintype "bidirectional"))
    )
    (net (code "70") (name "Net-(VR2-FB)") (class "Default")
      (node (ref "R34") (pin "1") (pinfunction "1_1") (pintype "passive"))
      (node (ref "R36") (pin "2") (pinfunction "2_2") (pintype "passive"))
      (node (ref "VR2") (pin "4") (pinfunction "FB_4") (pintype "bidirectional"))
    )
    (net (code "71") (name "Net-(VR2-SW)") (class "Default")
      (node (ref "C39") (pin "2") (pinfunction "2_2") (pintype "passive"))
      (node (ref "L2") (pin "1") (pinfunction "1_1") (pintype "passive"))
      (node (ref "R34") (pin "2") (pinfunction "2_2") (pintype "passive"))
      (node (ref "VR2") (pin "2") (pinfunction "SW_2") (pintype "bidirectional"))
    )
    (net (code "72") (name "PLATE_CURR_AMP") (class "Default")
      (node (ref "R51") (pin "1") (pinfunction "1_1") (pintype "passive"))
      (node (ref "R53") (pin "1") (pinfunction "1_1") (pintype "passive"))
      (node (ref "U6") (pin "3") (pinfunction "VIN_3") (pintype "input"))
    )
    (net (code "73") (name "PLATE_CURR_FAULT") (class "Default")
      (node (ref "TP1") (pin "TP") (pinfunction "TP_TP") (pintype "input"))
      (node (ref "U7") (pin "9") (pinfunction "~{FAULTB}_9") (pintype "bidirectional"))
    )
    (net (code "74") (name "PLATE_CURR_OUT") (class "Default")
      (node (ref "IC2") (pin "1") (pinfunction "+IN_1") (pintype "input"))
      (node (ref "R53") (pin "2") (pinfunction "2_2") (pintype "passive"))
      (node (ref "U7") (pin "12") (pinfunction "VOUT_12") (pintype "bidirectional"))
    )
    (net (code "75") (name "VALVE_-30V") (class "Default")
      (node (ref "U5") (pin "5") (pinfunction "IP-_5") (pintype "bidirectional"))
      (node (ref "U5") (pin "6") (pinfunction "IP-_6") (pintype "bidirectional"))
      (node (ref "U5") (pin "7") (pinfunction "IP-_7") (pintype "bidirectional"))
      (node (ref "U5") (pin "8") (pinfunction "IP-_8") (pintype "bidirectional"))
      (node (ref "X7") (pin "1") (pinfunction "1_1") (pintype "passive"))
    )
    (net (code "76") (name "VALVE_-30V_GEN") (class "Default")
      (node (ref "C31") (pin "2") (pinfunction "2_2") (pintype "passive"))
      (node (ref "C32") (pin "2") (pinfunction "2_2") (pintype "passive"))
      (node (ref "C33") (pin "2") (pinfunction "2_2") (pintype "passive"))
      (node (ref "C34") (pin "2") (pinfunction "2_2") (pintype "passive"))
      (node (ref "D10") (pin "A") (pinfunction "A_A") (pintype "passive"))
      (node (ref "D9") (pin "A") (pinfunction "A_A") (pintype "passive"))
      (node (ref "U5") (pin "1") (pinfunction "IP+_1") (pintype "bidirectional"))
      (node (ref "U5") (pin "2") (pinfunction "IP+_2") (pintype "bidirectional"))
      (node (ref "U5") (pin "3") (pinfunction "IP+_3") (pintype "bidirectional"))
      (node (ref "U5") (pin "4") (pinfunction "IP+_4") (pintype "bidirectional"))
    )
    (net (code "77") (name "VALVE_2.5KV") (class "Default")
      (node (ref "C57") (pin "1") (pinfunction "1_1") (pintype "passive"))
      (node (ref "C58") (pin "1") (pinfunction "1_1") (pintype "passive"))
      (node (ref "C59") (pin "1") (pinfunction "1_1") (pintype "passive"))
      (node (ref "C60") (pin "+VE") (pinfunction "+_+VE") (pintype "passive"))
      (node (ref "D11") (pin "1") (pinfunction "CATHODE_1") (pintype "bidirectional"))
      (node (ref "D12") (pin "1") (pinfunction "CATHODE_1") (pintype "bidirectional"))
      (node (ref "R1") (pin "1") (pinfunction "1_1") (pintype "passive"))
      (node (ref "R37") (pin "2") (pinfunction "2_2") (pintype "passive"))
      (node (ref "R38") (pin "2") (pinfunction "2_2") (pintype "passive"))
      (node (ref "X14") (pin "1") (pinfunction "1_1") (pintype "passive"))
      (node (ref "X14") (pin "2") (pinfunction "2_2") (pintype "passive"))
    )
    (net (code "78") (name "VALVE_5V") (class "Default")
      (node (ref "C11") (pin "1") (pinfunction "1_1") (pintype "passive"))
      (node (ref "C12") (pin "1") (pinfunction "1_1") (pintype "passive"))
      (node (ref "C14") (pin "1") (pinfunction "1_1") (pintype "passive"))
      (node (ref "C16") (pin "1") (pinfunction "1_1") (pintype "passive"))
      (node (ref "C18") (pin "1") (pinfunction "1_1") (pintype "passive"))
      (node (ref "C2") (pin "1") (pinfunction "1_1") (pintype "passive"))
      (node (ref "C20") (pin "1") (pinfunction "1_1") (pintype "passive"))
      (node (ref "C3") (pin "1") (pinfunction "1_1") (pintype "passive"))
      (node (ref "C35") (pin "1") (pinfunction "1_1") (pintype "passive"))
      (node (ref "C36") (pin "1") (pinfunction "1_1") (pintype "passive"))
      (node (ref "C37") (pin "1") (pinfunction "1_1") (pintype "passive"))
      (node (ref "C38") (pin "1") (pinfunction "1_1") (pintype "passive"))
      (node (ref "C5") (pin "1") (pinfunction "1_1") (pintype "passive"))
      (node (ref "C6") (pin "1") (pinfunction "1_1") (pintype "passive"))
      (node (ref "C8") (pin "1") (pinfunction "1_1") (pintype "passive"))
      (node (ref "C9") (pin "1") (pinfunction "1_1") (pintype "passive"))
      (node (ref "D1") (pin "C") (pinfunction "CATHODE_C") (pintype "bidirectional"))
      (node (ref "P2") (pin "1") (pinfunction "1_1") (pintype "passive"))
      (node (ref "P2") (pin "2") (pinfunction "2_2") (pintype "passive"))
      (node (ref "P2") (pin "3") (pinfunction "3_3") (pintype "passive"))
      (node (ref "P2") (pin "4") (pinfunction "4_4") (pintype "passive"))
      (node (ref "P2") (pin "5") (pinfunction "5_5") (pintype "passive"))
      (node (ref "P2") (pin "6") (pinfunction "6_6") (pintype "passive"))
      (node (ref "P2") (pin "7") (pinfunction "7_7") (pintype "passive"))
      (node (ref "P2") (pin "8") (pinfunction "8_8") (pintype "passive"))
      (node (ref "R18") (pin "2") (pinfunction "2_2") (pintype "passive"))
      (node (ref "R5") (pin "2") (pinfunction "2_2") (pintype "passive"))
      (node (ref "U1") (pin "1") (pinfunction "VA_1") (pintype "power_in"))
      (node (ref "U2") (pin "16") (pinfunction "VDD2_16") (pintype "power_in"))
      (node (ref "U3") (pin "16") (pinfunction "VDD2_16") (pintype "power_in"))
      (node (ref "VR1") (pin "+V") (pinfunction "V+_+V") (pintype "passive"))
      (node (ref "X9") (pin "2") (pinfunction "2_2") (pintype "passive"))
    )
    (net (code "79") (name "VALVE_6V3") (class "Default")
      (node (ref "C27") (pin "1") (pinfunction "1_1") (pintype "passive"))
      (node (ref "C28") (pin "1") (pinfunction "1_1") (pintype "passive"))
      (node (ref "C29") (pin "1") (pinfunction "1_1") (pintype "passive"))
      (node (ref "C30") (pin "1") (pinfunction "1_1") (pintype "passive"))
      (node (ref "D3") (pin "C") (pinfunction "C_C") (pintype "passive"))
      (node (ref "D4") (pin "C") (pinfunction "C_C") (pintype "passive"))
      (node (ref "X2") (pin "2") (pinfunction "2_2") (pintype "passive"))
    )
    (net (code "80") (name "VALVE_GND") (class "Default")
      (node (ref "C11") (pin "2") (pinfunction "2_2") (pintype "passive"))
      (node (ref "C12") (pin "2") (pinfunction "2_2") (pintype "passive"))
      (node (ref "C14") (pin "2") (pinfunction "2_2") (pintype "passive"))
      (node (ref "C16") (pin "2") (pinfunction "2_2") (pintype "passive"))
      (node (ref "C18") (pin "2") (pinfunction "2_2") (pintype "passive"))
      (node (ref "C2") (pin "2") (pinfunction "2_2") (pintype "passive"))
      (node (ref "C20") (pin "2") (pinfunction "2_2") (pintype "passive"))
      (node (ref "C27") (pin "2") (pinfunction "2_2") (pintype "passive"))
      (node (ref "C28") (pin "2") (pinfunction "2_2") (pintype "passive"))
      (node (ref "C29") (pin "2") (pinfunction "2_2") (pintype "passive"))
      (node (ref "C3") (pin "2") (pinfunction "2_2") (pintype "passive"))
      (node (ref "C30") (pin "2") (pinfunction "2_2") (pintype "passive"))
      (node (ref "C31") (pin "1") (pinfunction "1_1") (pintype "passive"))
      (node (ref "C32") (pin "1") (pinfunction "1_1") (pintype "passive"))
      (node (ref "C33") (pin "1") (pinfunction "1_1") (pintype "passive"))
      (node (ref "C34") (pin "1") (pinfunction "1_1") (pintype "passive"))
      (node (ref "C35") (pin "2") (pinfunction "2_2") (pintype "passive"))
      (node (ref "C36") (pin "2") (pinfunction "2_2") (pintype "passive"))
      (node (ref "C37") (pin "2") (pinfunction "2_2") (pintype "passive"))
      (node (ref "C38") (pin "2") (pinfunction "2_2") (pintype "passive"))
      (node (ref "C5") (pin "2") (pinfunction "2_2") (pintype "passive"))
      (node (ref "C6") (pin "2") (pinfunction "2_2") (pintype "passive"))
      (node (ref "C8") (pin "2") (pinfunction "2_2") (pintype "passive"))
      (node (ref "C87") (pin "2") (pinfunction "2_2") (pintype "passive"))
      (node (ref "C9") (pin "2") (pinfunction "2_2") (pintype "passive"))
      (node (ref "D2") (pin "A") (pinfunction "ANODE_A") (pintype "bidirectional"))
      (node (ref "D5") (pin "A") (pinfunction "A_A") (pintype "passive"))
      (node (ref "D6") (pin "A") (pinfunction "A_A") (pintype "passive"))
      (node (ref "D7") (pin "C") (pinfunction "C_C") (pintype "passive"))
      (node (ref "D8") (pin "C") (pinfunction "C_C") (pintype "passive"))
      (node (ref "P2") (pin "14") (pinfunction "14_14") (pintype "passive"))
      (node (ref "P2") (pin "15") (pinfunction "15_15") (pintype "passive"))
      (node (ref "P2") (pin "16") (pinfunction "16_16") (pintype "passive"))
      (node (ref "P2") (pin "17") (pinfunction "17_17") (pintype "passive"))
      (node (ref "P2") (pin "18") (pinfunction "18_18") (pintype "passive"))
      (node (ref "P2") (pin "19") (pinfunction "19_19") (pintype "passive"))
      (node (ref "P2") (pin "20") (pinfunction "20_20") (pintype "passive"))
      (node (ref "R15") (pin "1") (pinfunction "1_1") (pintype "passive"))
      (node (ref "R30") (pin "1") (pinfunction "1_1") (pintype "passive"))
      (node (ref "R31") (pin "1") (pinfunction "1_1") (pintype "passive"))
      (node (ref "U1") (pin "2") (pinfunction "GND_2") (pintype "power_in"))
      (node (ref "U2") (pin "15") (pinfunction "GND2_15") (pintype "power_in"))
      (node (ref "U2") (pin "9") (pinfunction "GND2_9") (pintype "power_in"))
      (node (ref "U3") (pin "15") (pinfunction "GND2_15") (pintype "power_in"))
      (node (ref "U3") (pin "9") (pinfunction "GND2_9") (pintype "power_in"))
      (node (ref "U7") (pin "5") (pinfunction "IP-_5") (pintype "bidirectional"))
      (node (ref "U7") (pin "6") (pinfunction "IP-_6") (pintype "bidirectional"))
      (node (ref "U7") (pin "7") (pinfunction "IP-_7") (pintype "bidirectional"))
      (node (ref "U7") (pin "8") (pinfunction "IP-_8") (pintype "bidirectional"))
      (node (ref "VR1") (pin "-V") (pinfunction "V-_-V") (pintype "passive"))
      (node (ref "X17") (pin "1") (pinfunction "1_1") (pintype "passive"))
      (node (ref "X17") (pin "2") (pinfunction "2_2") (pintype "passive"))
      (node (ref "X2") (pin "1") (pinfunction "1_1") (pintype "passive"))
      (node (ref "X7") (pin "2") (pinfunction "2_2") (pintype "passive"))
      (node (ref "X9") (pin "1") (pinfunction "1_1") (pintype "passive"))
    )
    (net (code "81") (name "VALVE_LOW") (class "Default")
      (node (ref "C61") (pin "2") (pinfunction "2_2") (pintype "passive"))
      (node (ref "C62") (pin "2") (pinfunction "2_2") (pintype "passive"))
      (node (ref "C63") (pin "2") (pinfunction "2_2") (pintype "passive"))
      (node (ref "C82") (pin "-VE") (pinfunction "-_-VE") (pintype "passive"))
      (node (ref "C87") (pin "1") (pinfunction "1_1") (pintype "passive"))
      (node (ref "D17") (pin "3") (pinfunction "ANODE_3") (pintype "bidirectional"))
      (node (ref "D18") (pin "3") (pinfunction "ANODE_3") (pintype "bidirectional"))
      (node (ref "R39") (pin "1") (pinfunction "1_1") (pintype "passive"))
      (node (ref "R50") (pin "1") (pinfunction "1_1") (pintype "passive"))
      (node (ref "U7") (pin "1") (pinfunction "IP+_1") (pintype "bidirectional"))
      (node (ref "U7") (pin "2") (pinfunction "IP+_2") (pintype "bidirectional"))
      (node (ref "U7") (pin "3") (pinfunction "IP+_3") (pintype "bidirectional"))
      (node (ref "U7") (pin "4") (pinfunction "IP+_4") (pintype "bidirectional"))
    )
    (net (code "82") (name "VALVE_MISO") (class "Default")
      (node (ref "P1") (pin "5") (pinfunction "5_5") (pintype "passive"))
      (node (ref "R16") (pin "1") (pinfunction "1_1") (pintype "passive"))
      (node (ref "U4") (pin "5") (pinfunction "SDATA_5") (pintype "output"))
      (node (ref "U6") (pin "5") (pinfunction "SDATA_5") (pintype "output"))
    )
    (net (code "83") (name "VALVE_MOSI") (class "Default")
      (node (ref "P1") (pin "7") (pinfunction "7_7") (pintype "passive"))
      (node (ref "R13") (pin "1") (pinfunction "1_1") (pintype "passive"))
    )
    (net (code "84") (name "VALVE_SCLK") (class "Default")
      (node (ref "P1") (pin "8") (pinfunction "8_8") (pintype "passive"))
      (node (ref "R11") (pin "1") (pinfunction "1_1") (pintype "passive"))
      (node (ref "U4") (pin "4") (pinfunction "SCLK_4") (pintype "input"))
      (node (ref "U6") (pin "4") (pinfunction "SCLK_4") (pintype "input"))
    )
    (net (code "85") (name "V_MISO") (class "Default")
      (node (ref "P2") (pin "11") (pinfunction "11_11") (pintype "passive"))
      (node (ref "R17") (pin "2") (pinfunction "2_2") (pintype "passive"))
      (node (ref "U1") (pin "5") (pinfunction "SDATA_5") (pintype "output"))
    )
    (net (code "86") (name "V_MOSI") (class "Default")
      (node (ref "P2") (pin "13") (pinfunction "13_13") (pintype "passive"))
      (node (ref "R14") (pin "2") (pinfunction "2_2") (pintype "passive"))
    )
    (net (code "87") (name "V_SCLK") (class "Default")
      (node (ref "P2") (pin "12") (pinfunction "12_12") (pintype "passive"))
      (node (ref "R12") (pin "2") (pinfunction "2_2") (pintype "passive"))
      (node (ref "U1") (pin "4") (pinfunction "SCLK_4") (pintype "input"))
    )
    (net (code "88") (name "unconnected-(R25-Pad2)") (class "Default")
      (node (ref "R25") (pin "2") (pinfunction "2_2") (pintype "passive"))
    )
    (net (code "89") (name "unconnected-(R27-Pad2)") (class "Default")
      (node (ref "R27") (pin "2") (pinfunction "2_2") (pintype "passive"))
    )
    (net (code "90") (name "~{VALVE_GRID_CUR_SS}") (class "Default")
      (node (ref "P1") (pin "1") (pinfunction "1_1") (pintype "passive"))
      (node (ref "U4") (pin "6") (pinfunction "~{CS}_6") (pintype "passive"))
    )
    (net (code "91") (name "~{VALVE_OUT_FWD_SS}") (class "Default")
      (node (ref "P1") (pin "3") (pinfunction "3_3") (pintype "passive"))
      (node (ref "R20") (pin "1") (pinfunction "1_1") (pintype "passive"))
    )
    (net (code "92") (name "~{VALVE_OUT_RVS_SS}") (class "Default")
      (node (ref "P1") (pin "4") (pinfunction "4_4") (pintype "passive"))
      (node (ref "R22") (pin "1") (pinfunction "1_1") (pintype "passive"))
    )
    (net (code "93") (name "~{VALVE_PLATE_CUR_SS}") (class "Default")
      (node (ref "P1") (pin "2") (pinfunction "2_2") (pintype "passive"))
      (node (ref "U6") (pin "6") (pinfunction "~{CS}_6") (pintype "passive"))
    )
    (net (code "94") (name "~{VALVE_VOLT_SS}") (class "Default")
      (node (ref "P1") (pin "6") (pinfunction "6_6") (pintype "passive"))
      (node (ref "R9") (pin "1") (pinfunction "1_1") (pintype "passive"))
    )
    (net (code "95") (name "~{V_OUT_FWD_SS}") (class "Default")
      (node (ref "P2") (pin "9") (pinfunction "9_9") (pintype "passive"))
      (node (ref "R21") (pin "2") (pinfunction "2_2") (pintype "passive"))
    )
    (net (code "96") (name "~{V_OUT_RVS_SS}") (class "Default")
      (node (ref "P2") (pin "10") (pinfunction "10_10") (pintype "passive"))
      (node (ref "R23") (pin "2") (pinfunction "2_2") (pintype "passive"))
    )
  )
)
